# ft600hx4k.net
KiCad netlist of a schematic drawn in Altium Designer
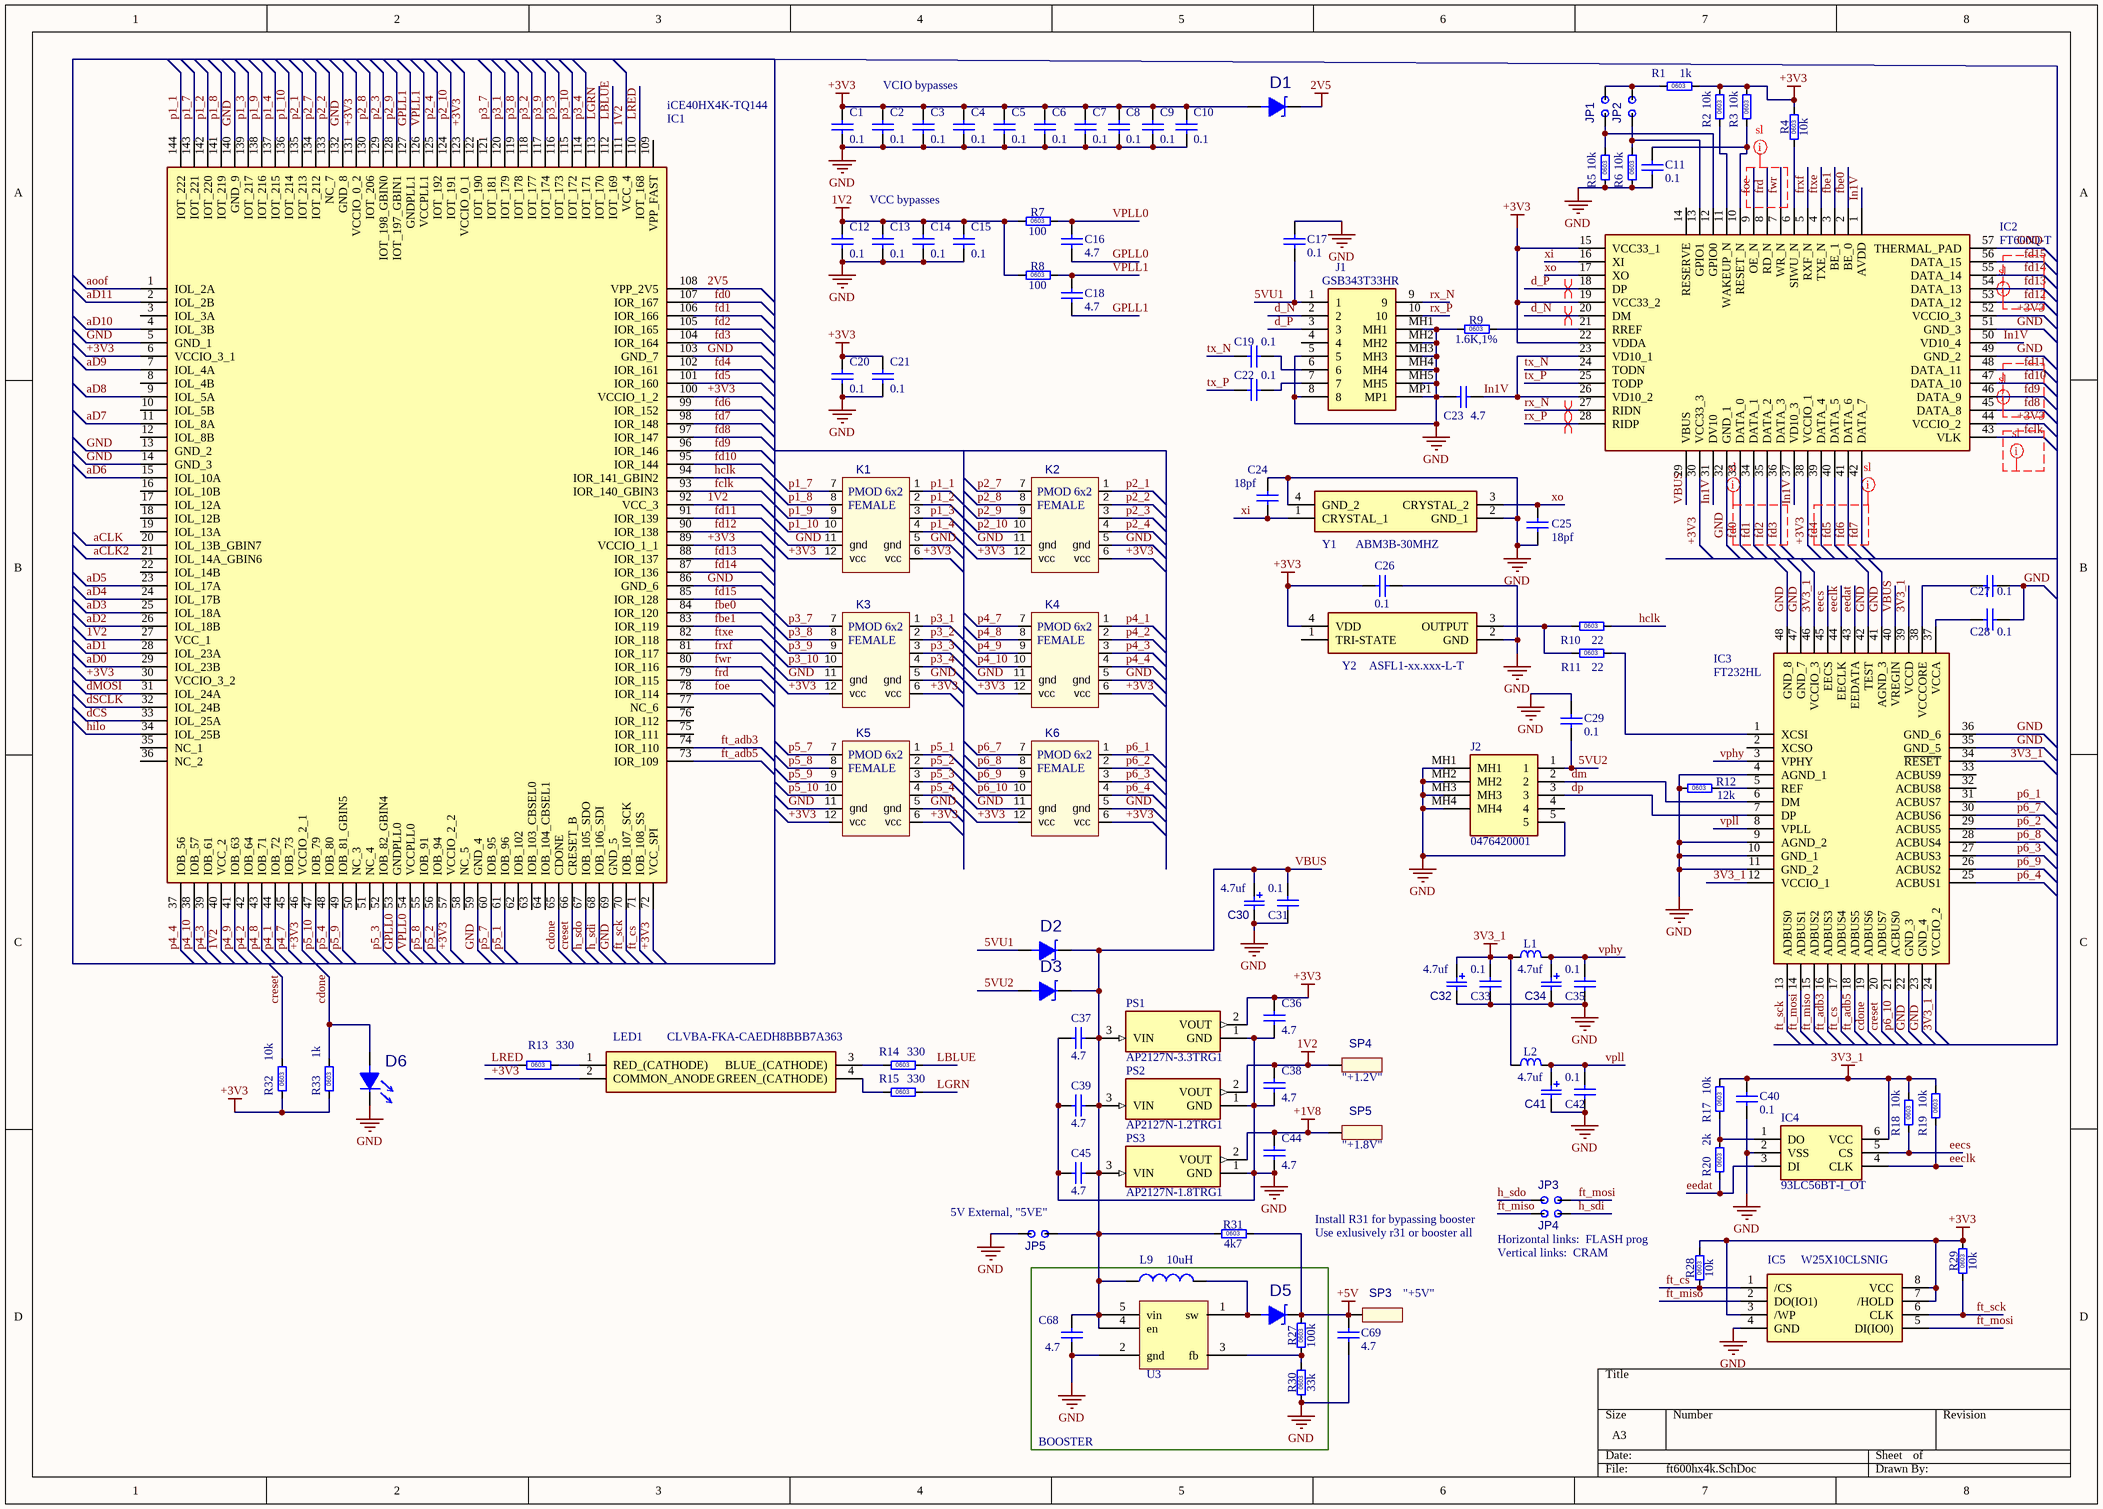
[diagram p0: ft600hx4k.SchDoc]

(export (version "E")
  (design (tool "Eeschema 10.0.6"))
  (components
    (comp (ref "C1")
      (value "0.1")
      (footprint "SM0603 _3D_cap")
      (description "Capacitor  0603 inch")
      (fields (field (name "Comment") "cap0603") (field (name "PUBLISHER") "Altium Limited"))
      (libsource (lib "alt2017") (part "cap0603"))
    )
    (comp (ref "C2")
      (value "0.1")
      (footprint "SM0603 _3D_cap")
      (description "Capacitor  0603 inch")
      (fields (field (name "Comment") "cap0603") (field (name "PUBLISHER") "Altium Limited"))
      (libsource (lib "alt2017") (part "cap0603"))
    )
    (comp (ref "C3")
      (value "0.1")
      (footprint "SM0603 _3D_cap")
      (description "Capacitor  0603 inch")
      (fields (field (name "Comment") "cap0603") (field (name "PUBLISHER") "Altium Limited"))
      (libsource (lib "alt2017") (part "cap0603"))
    )
    (comp (ref "C4")
      (value "0.1")
      (footprint "SM0603 _3D_cap")
      (description "Capacitor  0603 inch")
      (fields (field (name "Comment") "cap0603") (field (name "PUBLISHER") "Altium Limited"))
      (libsource (lib "alt2017") (part "cap0603"))
    )
    (comp (ref "C5")
      (value "0.1")
      (footprint "SM0603 _3D_cap")
      (description "Capacitor  0603 inch")
      (fields (field (name "Comment") "cap0603") (field (name "PUBLISHER") "Altium Limited"))
      (libsource (lib "alt2017") (part "cap0603"))
    )
    (comp (ref "C6")
      (value "0.1")
      (footprint "SM0603 _3D_cap")
      (description "Capacitor  0603 inch")
      (fields (field (name "Comment") "cap0603") (field (name "PUBLISHER") "Altium Limited"))
      (libsource (lib "alt2017") (part "cap0603"))
    )
    (comp (ref "C7")
      (value "0.1")
      (footprint "SM0603 _3D_cap")
      (description "Capacitor  0603 inch")
      (fields (field (name "Comment") "cap0603") (field (name "PUBLISHER") "Altium Limited"))
      (libsource (lib "alt2017") (part "cap0603"))
    )
    (comp (ref "C8")
      (value "0.1")
      (footprint "SM0603 _3D_cap")
      (description "Capacitor  0603 inch")
      (fields (field (name "Comment") "cap0603") (field (name "PUBLISHER") "Altium Limited"))
      (libsource (lib "alt2017") (part "cap0603"))
    )
    (comp (ref "C9")
      (value "0.1")
      (footprint "SM0603 _3D_cap")
      (description "Capacitor  0603 inch")
      (fields (field (name "Comment") "cap0603") (field (name "PUBLISHER") "Altium Limited"))
      (libsource (lib "alt2017") (part "cap0603"))
    )
    (comp (ref "C10")
      (value "0.1")
      (footprint "SM0603 _3D_cap")
      (description "Capacitor  0603 inch")
      (fields (field (name "Comment") "cap0603") (field (name "PUBLISHER") "Altium Limited"))
      (libsource (lib "alt2017") (part "cap0603"))
    )
    (comp (ref "C11")
      (value "0.1")
      (footprint "SM0603 _3D_cap")
      (description "Capacitor  0603 inch")
      (fields (field (name "Comment") "cap0603") (field (name "PUBLISHER") "Altium Limited"))
      (libsource (lib "alt2017") (part "cap0603"))
    )
    (comp (ref "C12")
      (value "0.1")
      (footprint "SM0603 _3D_cap")
      (description "Capacitor  0603 inch")
      (fields (field (name "Comment") "cap0603") (field (name "PUBLISHER") "Altium Limited"))
      (libsource (lib "alt2017") (part "cap0603"))
    )
    (comp (ref "C13")
      (value "0.1")
      (footprint "SM0603 _3D_cap")
      (description "Capacitor  0603 inch")
      (fields (field (name "Comment") "cap0603") (field (name "PUBLISHER") "Altium Limited"))
      (libsource (lib "alt2017") (part "cap0603"))
    )
    (comp (ref "C14")
      (value "0.1")
      (footprint "SM0603 _3D_cap")
      (description "Capacitor  0603 inch")
      (fields (field (name "Comment") "cap0603") (field (name "PUBLISHER") "Altium Limited"))
      (libsource (lib "alt2017") (part "cap0603"))
    )
    (comp (ref "C15")
      (value "0.1")
      (footprint "SM0603 _3D_cap")
      (description "Capacitor  0603 inch")
      (fields (field (name "Comment") "cap0603") (field (name "PUBLISHER") "Altium Limited"))
      (libsource (lib "alt2017") (part "cap0603"))
    )
    (comp (ref "C16")
      (value "4.7")
      (footprint "SM0603 _3D_cap")
      (description "Capacitor  0603 inch")
      (fields (field (name "Comment") "cap0603") (field (name "PUBLISHER") "Altium Limited"))
      (libsource (lib "alt2017") (part "cap0603"))
    )
    (comp (ref "C17")
      (value "0.1")
      (footprint "SM0603 _3D_cap")
      (description "Capacitor  0603 inch")
      (fields (field (name "Comment") "cap0603") (field (name "PUBLISHER") "Altium Limited"))
      (libsource (lib "alt2017") (part "cap0603"))
    )
    (comp (ref "C18")
      (value "4.7")
      (footprint "SM0603 _3D_cap")
      (description "Capacitor  0603 inch")
      (fields (field (name "Comment") "cap0603") (field (name "PUBLISHER") "Altium Limited"))
      (libsource (lib "alt2017") (part "cap0603"))
    )
    (comp (ref "C19")
      (value "0.1")
      (footprint "SM0603 _3D_cap")
      (description "Capacitor  0603 inch")
      (fields (field (name "Comment") "cap0603") (field (name "PUBLISHER") "Altium Limited"))
      (libsource (lib "alt2017") (part "cap0603"))
    )
    (comp (ref "C20")
      (value "0.1")
      (footprint "SM0603 _3D_cap")
      (description "Capacitor  0603 inch")
      (fields (field (name "Comment") "cap0603") (field (name "PUBLISHER") "Altium Limited"))
      (libsource (lib "alt2017") (part "cap0603"))
    )
    (comp (ref "C21")
      (value "0.1")
      (footprint "SM0603 _3D_cap")
      (description "Capacitor  0603 inch")
      (fields (field (name "Comment") "cap0603") (field (name "PUBLISHER") "Altium Limited"))
      (libsource (lib "alt2017") (part "cap0603"))
    )
    (comp (ref "C22")
      (value "0.1")
      (footprint "SM0603 _3D_cap")
      (description "Capacitor  0603 inch")
      (fields (field (name "Comment") "cap0603") (field (name "PUBLISHER") "Altium Limited"))
      (libsource (lib "alt2017") (part "cap0603"))
    )
    (comp (ref "C23")
      (value "4.7")
      (footprint "SM0603 _3D_cap")
      (description "Capacitor  0603 inch")
      (fields (field (name "Comment") "cap0603") (field (name "PUBLISHER") "Altium Limited"))
      (libsource (lib "alt2017") (part "cap0603"))
    )
    (comp (ref "C24")
      (value "18pf")
      (footprint "SM0603 _3D_cap")
      (description "Capacitor  0603 inch")
      (fields (field (name "Comment") "cap0603") (field (name "PUBLISHER") "Altium Limited"))
      (libsource (lib "alt2017") (part "cap0603"))
    )
    (comp (ref "C25")
      (value "18pf")
      (footprint "SM0603 _3D_cap")
      (description "Capacitor  0603 inch")
      (fields (field (name "Comment") "cap0603") (field (name "PUBLISHER") "Altium Limited"))
      (libsource (lib "alt2017") (part "cap0603"))
    )
    (comp (ref "C26")
      (value "0.1")
      (footprint "SM0603 _3D_cap")
      (description "Capacitor  0603 inch")
      (fields (field (name "Comment") "cap0603") (field (name "PUBLISHER") "Altium Limited"))
      (libsource (lib "alt2017") (part "cap0603"))
    )
    (comp (ref "C27")
      (value "0.1")
      (footprint "SM0603 _3D_cap")
      (description "Capacitor  0603 inch")
      (fields (field (name "Comment") "cap0603") (field (name "PUBLISHER") "Altium Limited"))
      (libsource (lib "alt2017") (part "cap0603"))
    )
    (comp (ref "C28")
      (value "0.1")
      (footprint "SM0603 _3D_cap")
      (description "Capacitor  0603 inch")
      (fields (field (name "Comment") "cap0603") (field (name "PUBLISHER") "Altium Limited"))
      (libsource (lib "alt2017") (part "cap0603"))
    )
    (comp (ref "C29")
      (value "0.1")
      (footprint "SM0603 _3D_cap")
      (description "Capacitor  0603 inch")
      (fields (field (name "Comment") "cap0603") (field (name "PUBLISHER") "Altium Limited"))
      (libsource (lib "alt2017") (part "cap0603"))
    )
    (comp (ref "C30")
      (value "CAP_POL_SMA")
      (footprint "CAP_POL_SMA (3216)")
      (description "CAP_POL_SMA(3216)")
      (fields (field (name "ALTIUM_UNNAMED_1") "4.7uf"))
      (libsource (lib "alt2017") (part "CAP_POL_SMA"))
    )
    (comp (ref "C31")
      (value "0.1")
      (footprint "SM0603 _3D_cap")
      (description "Capacitor  0603 inch")
      (fields (field (name "Comment") "cap0603") (field (name "PUBLISHER") "Altium Limited"))
      (libsource (lib "alt2017") (part "cap0603"))
    )
    (comp (ref "C32")
      (value "CAP_POL_SMA")
      (footprint "CAP_POL_SMA (3216)")
      (description "CAP_POL_SMA(3216)")
      (fields (field (name "ALTIUM_UNNAMED_1") "4.7uf"))
      (libsource (lib "alt2017") (part "CAP_POL_SMA"))
    )
    (comp (ref "C33")
      (value "0.1")
      (footprint "SM0603 _3D_cap")
      (description "Capacitor  0603 inch")
      (fields (field (name "Comment") "cap0603") (field (name "PUBLISHER") "Altium Limited"))
      (libsource (lib "alt2017") (part "cap0603"))
    )
    (comp (ref "C34")
      (value "CAP_POL_SMA")
      (footprint "CAP_POL_SMA (3216)")
      (description "CAP_POL_SMA(3216)")
      (fields (field (name "ALTIUM_UNNAMED_1") "4.7uf"))
      (libsource (lib "alt2017") (part "CAP_POL_SMA"))
    )
    (comp (ref "C35")
      (value "0.1")
      (footprint "SM0603 _3D_cap")
      (description "Capacitor  0603 inch")
      (fields (field (name "Comment") "cap0603") (field (name "PUBLISHER") "Altium Limited"))
      (libsource (lib "alt2017") (part "cap0603"))
    )
    (comp (ref "C36")
      (value "4.7")
      (footprint "SM0603 _3D_cap")
      (description "Capacitor  0603 inch")
      (fields (field (name "Comment") "cap0603") (field (name "PUBLISHER") "Altium Limited"))
      (libsource (lib "alt2017") (part "cap0603"))
    )
    (comp (ref "C37")
      (value "4.7")
      (footprint "SM0603 _3D_cap")
      (description "Capacitor  0603 inch")
      (fields (field (name "Comment") "cap0603") (field (name "PUBLISHER") "Altium Limited"))
      (libsource (lib "alt2017") (part "cap0603"))
    )
    (comp (ref "C38")
      (value "4.7")
      (footprint "SM0603 _3D_cap")
      (description "Capacitor  0603 inch")
      (fields (field (name "Comment") "cap0603") (field (name "PUBLISHER") "Altium Limited"))
      (libsource (lib "alt2017") (part "cap0603"))
    )
    (comp (ref "C39")
      (value "4.7")
      (footprint "SM0603 _3D_cap")
      (description "Capacitor  0603 inch")
      (fields (field (name "Comment") "cap0603") (field (name "PUBLISHER") "Altium Limited"))
      (libsource (lib "alt2017") (part "cap0603"))
    )
    (comp (ref "C40")
      (value "0.1")
      (footprint "SM0603 _3D_cap")
      (description "Capacitor  0603 inch")
      (fields (field (name "Comment") "cap0603") (field (name "PUBLISHER") "Altium Limited"))
      (libsource (lib "alt2017") (part "cap0603"))
    )
    (comp (ref "C41")
      (value "CAP_POL_SMA")
      (footprint "CAP_POL_SMA (3216)")
      (description "CAP_POL_SMA(3216)")
      (fields (field (name "ALTIUM_UNNAMED_1") "4.7uf"))
      (libsource (lib "alt2017") (part "CAP_POL_SMA"))
    )
    (comp (ref "C42")
      (value "0.1")
      (footprint "SM0603 _3D_cap")
      (description "Capacitor  0603 inch")
      (fields (field (name "Comment") "cap0603") (field (name "PUBLISHER") "Altium Limited"))
      (libsource (lib "alt2017") (part "cap0603"))
    )
    (comp (ref "C44")
      (value "4.7")
      (footprint "SM0603 _3D_cap")
      (description "Capacitor  0603 inch")
      (fields (field (name "Comment") "cap0603") (field (name "PUBLISHER") "Altium Limited"))
      (libsource (lib "alt2017") (part "cap0603"))
    )
    (comp (ref "C45")
      (value "4.7")
      (footprint "SM0603 _3D_cap")
      (description "Capacitor  0603 inch")
      (fields (field (name "Comment") "cap0603") (field (name "PUBLISHER") "Altium Limited"))
      (libsource (lib "alt2017") (part "cap0603"))
    )
    (comp (ref "C68")
      (value "4.7")
      (footprint "SM0603 _3D_cap")
      (description "Capacitor  0603 inch")
      (fields (field (name "Comment") "cap0603") (field (name "PUBLISHER") "Altium Limited"))
      (libsource (lib "alt2017") (part "cap0603"))
    )
    (comp (ref "C69")
      (value "4.7")
      (footprint "SM0603 _3D_cap")
      (description "Capacitor  0603 inch")
      (fields (field (name "Comment") "cap0603") (field (name "PUBLISHER") "Altium Limited"))
      (libsource (lib "alt2017") (part "cap0603"))
    )
    (comp (ref "D1")
      (value "DiodeShottky_SOD323")
      (footprint "SOD323")
      (description "SOD323")
      (libsource (lib "alt2017") (part "DiodeShottky_SOD323"))
    )
    (comp (ref "D2")
      (value "DiodeShottky_SOD323")
      (footprint "SOD323")
      (description "SOD323")
      (libsource (lib "alt2017") (part "DiodeShottky_SOD323"))
    )
    (comp (ref "D3")
      (value "DiodeShottky_SOD323")
      (footprint "SOD323")
      (description "SOD323")
      (libsource (lib "alt2017") (part "DiodeShottky_SOD323"))
    )
    (comp (ref "D5")
      (value "DiodeShottky_SOD323")
      (footprint "SOD323")
      (description "SOD323")
      (libsource (lib "alt2017") (part "DiodeShottky_SOD323"))
    )
    (comp (ref "D6")
      (value "LIGHT_SM0805")
      (footprint "SM0805_diode")
      (libsource (lib "alt2017") (part "LIGHT_SM0805"))
    )
    (comp (ref "IC1")
      (value "iCE40HX4K-TQ144")
      (footprint "SamacSys:QFP50P2200X2200X160-144N")
      (description "Integrated Circuit")
      (fields
        (field (name "MOUSER PART NUMBER") "842-ICE40HX4K-TQ144")
        (field (name "ARROW PART NUMBER") "ICE40HX4K-TQ144")
      )
      (libsource (lib "*") (part "iCE40HX4K-TQ144"))
    )
    (comp (ref "IC2")
      (value "FT600Q-T")
      (footprint "SamacSys:QFN40P700X700X90-57N-D")
      (description "Integrated Circuit")
      (fields (field (name "MOUSER PART NUMBER") "895-FT600Q-T"))
      (libsource (lib "SamacSys") (part "FT600Q-T"))
    )
    (comp (ref "IC3")
      (value "FT232HL")
      (footprint "SamacSys:QFP50P900X900X160-48N")
      (description "Integrated Circuit")
      (fields
        (field (name "MANUFACTURER_PART_NUMBER") "FT232HL-REEL")
        (field (name "MOUSER PART NUMBER") "895-FT232HL-REEL")
      )
      (libsource (lib "*") (part "FT232HL-REEL"))
    )
    (comp (ref "IC4")
      (value "93LC56BT-I_OT")
      (footprint "SamacSys:SOT95P270X145-6N")
      (description "Integrated Circuit")
      (fields
        (field (name "MANUFACTURER_PART_NUMBER") "93LC56BT-I/OT")
        (field (name "MOUSER PART NUMBER") "579-93LC56BT-I/OT")
      )
      (libsource (lib "*") (part "93LC56BT-I_OT"))
    )
    (comp (ref "IC5")
      (value "W25X10CLSNIG")
      (footprint "SamacSys:SOIC127P600X175-8N")
      (description "Integrated Circuit")
      (fields (field (name "MOUSER PART NUMBER") "454-W25X10CLSNIG"))
      (libsource (lib "*") (part "W25X10CLSNIG"))
    )
    (comp (ref "J1")
      (value "GSB343T33HR")
      (footprint "SamacSys:GSB343T33HR")
      (description "Connector")
      (fields (field (name "MOUSER PART NUMBER") "523-GSB343T33HR"))
      (libsource (lib "*") (part "GSB343T33HR"))
    )
    (comp (ref "J2")
      (value "0476420001")
      (footprint "SamacSys:0476420001")
      (description "Connector")
      (libsource (lib "*") (part "0476420001"))
    )
    (comp (ref "JP1") (value "JUMPER2") (footprint "JUMPER2") (libsource (lib "alt2017") (part "JUMPER2")))
    (comp (ref "JP2") (value "JUMPER2") (footprint "JUMPER2") (libsource (lib "alt2017") (part "JUMPER2")))
    (comp (ref "JP3") (value "JUMPER2") (footprint "JUMPER2") (libsource (lib "alt2017") (part "JUMPER2")))
    (comp (ref "JP4") (value "JUMPER2") (footprint "JUMPER2") (libsource (lib "alt2017") (part "JUMPER2")))
    (comp (ref "JP5") (value "JUMPER2") (footprint "JUMPER2") (libsource (lib "alt2017") (part "JUMPER2")))
    (comp (ref "K1")
      (value "PMOD_6x2_ra_female")
      (footprint "PMOD_6x2_RA_FEMALE")
      (description "PMOD_6x2_right_angle")
      (libsource (lib "alt_vovan") (part "PMOD_6x2_ra_female"))
    )
    (comp (ref "K2")
      (value "PMOD_6x2_ra_female")
      (footprint "PMOD_6x2_RA_FEMALE")
      (description "PMOD_6x2_right_angle")
      (libsource (lib "alt_vovan") (part "PMOD_6x2_ra_female"))
    )
    (comp (ref "K3")
      (value "PMOD_6x2_ra_female")
      (footprint "PMOD_6x2_RA_FEMALE")
      (description "PMOD_6x2_right_angle")
      (libsource (lib "alt_vovan") (part "PMOD_6x2_ra_female"))
    )
    (comp (ref "K4")
      (value "PMOD_6x2_ra_female")
      (footprint "PMOD_6x2_RA_FEMALE")
      (description "PMOD_6x2_right_angle")
      (libsource (lib "alt_vovan") (part "PMOD_6x2_ra_female"))
    )
    (comp (ref "K5")
      (value "PMOD_6x2_ra_female")
      (footprint "PMOD_6x2_RA_FEMALE")
      (description "PMOD_6x2_right_angle")
      (libsource (lib "alt_vovan") (part "PMOD_6x2_ra_female"))
    )
    (comp (ref "K6")
      (value "PMOD_6x2_ra_female")
      (footprint "PMOD_6x2_RA_FEMALE")
      (description "PMOD_6x2_right_angle")
      (libsource (lib "alt_vovan") (part "PMOD_6x2_ra_female"))
    )
    (comp (ref "L1")
      (value "75R@100MHz")
      (footprint "SM0603_3D_res")
      (description "chip inductance 0603")
      (fields
        (field (name "PART NUMBER") "IND0805_MURATA_BLM21BB750SN1D")
        (field (name "POWER") "700mA")
        (field (name "AUTHOR") "S. Jafar")
      )
      (libsource (lib "alt_vovan") (part "chip inductance 0603"))
    )
    (comp (ref "L2")
      (value "75R@100MHz")
      (footprint "SM0603_3D_res")
      (description "chip inductance 0603")
      (fields
        (field (name "PART NUMBER") "IND0805_MURATA_BLM21BB750SN1D")
        (field (name "POWER") "700mA")
        (field (name "AUTHOR") "S. Jafar")
      )
      (libsource (lib "alt_vovan") (part "chip inductance 0603"))
    )
    (comp (ref "L9")
      (value "inductance SMT 3.2x4.5 mm")
      (footprint "inductor_LQH43PN")
      (fields (field (name "ALTIUM_UNNAMED_1") "10uH"))
      (libsource (lib "alt2017") (part "inductor_LQH43PN"))
    )
    (comp (ref "LED1")
      (value "CLVBA-FKA-CAEDH8BBB7A363")
      (footprint "SamacSys:CLVBAFKACAEDH8BBB7A363")
      (description "LED")
      (fields (field (name "MOUSER PART NUMBER") "941-VBAFKACAEDH8B7A3"))
      (libsource (lib "*") (part "CLVBA-FKA-CAEDH8BBB7A363"))
    )
    (comp (ref "PS1")
      (value "AP2127N-3.3TRG1")
      (footprint "SamacSys:SOT89P240X110-3N")
      (description "Power Supply")
      (fields (field (name "MOUSER PART NUMBER") "621-AP2127N-3.3TRG1"))
      (libsource (lib "*") (part "AP2127N-3.3TRG1"))
    )
    (comp (ref "PS2")
      (value "AP2127N-1.2TRG1")
      (footprint "SamacSys:SOT89P240X110-3N")
      (description "Power Supply")
      (fields
        (field (name "MANUFACTURER_PART_NUMBER") "AP2127N-3.3TRG1")
        (field (name "MOUSER PART NUMBER") "621-AP2127N-3.3TRG1")
      )
      (libsource (lib "*") (part "AP2127N-3.3TRG1"))
    )
    (comp (ref "PS3")
      (value "AP2127N-1.8TRG1")
      (footprint "SamacSys:SOT89P240X110-3N")
      (description "Power Supply")
      (fields
        (field (name "MANUFACTURER_PART_NUMBER") "AP2127N-3.3TRG1")
        (field (name "MOUSER PART NUMBER") "621-AP2127N-3.3TRG1")
      )
      (libsource (lib "*") (part "AP2127N-3.3TRG1"))
    )
    (comp (ref "R1")
      (value "1k")
      (footprint "SM0603_3D_res")
      (description "Res_0603_EU")
      (fields
        (field (name "PART NUMBER") "R1206_4K7_1%_0.25W_100PPM")
        (field (name "POWER") "0.25W")
        (field (name "AUTHOR") "CERN DEM JLC")
      )
      (libsource (lib "alt_vovan") (part "Res_0603_EU"))
    )
    (comp (ref "R2")
      (value "10k")
      (footprint "SM0603_3D_res")
      (description "Res_0603_EU")
      (fields
        (field (name "PART NUMBER") "R1206_4K7_1%_0.25W_100PPM")
        (field (name "POWER") "0.25W")
        (field (name "AUTHOR") "CERN DEM JLC")
      )
      (libsource (lib "alt_vovan") (part "Res_0603_EU"))
    )
    (comp (ref "R3")
      (value "10k")
      (footprint "SM0603_3D_res")
      (description "Res_0603_EU")
      (fields
        (field (name "PART NUMBER") "R1206_4K7_1%_0.25W_100PPM")
        (field (name "POWER") "0.25W")
        (field (name "AUTHOR") "CERN DEM JLC")
      )
      (libsource (lib "alt_vovan") (part "Res_0603_EU"))
    )
    (comp (ref "R4")
      (value "10k")
      (footprint "SM0603_3D_res")
      (description "Res_0603_EU")
      (fields
        (field (name "PART NUMBER") "R1206_4K7_1%_0.25W_100PPM")
        (field (name "POWER") "0.25W")
        (field (name "AUTHOR") "CERN DEM JLC")
      )
      (libsource (lib "alt_vovan") (part "Res_0603_EU"))
    )
    (comp (ref "R5")
      (value "10k")
      (footprint "SM0603_3D_res")
      (description "Res_0603_EU")
      (fields
        (field (name "PART NUMBER") "R1206_4K7_1%_0.25W_100PPM")
        (field (name "POWER") "0.25W")
        (field (name "AUTHOR") "CERN DEM JLC")
      )
      (libsource (lib "alt_vovan") (part "Res_0603_EU"))
    )
    (comp (ref "R6")
      (value "10k")
      (footprint "SM0603_3D_res")
      (description "Res_0603_EU")
      (fields
        (field (name "PART NUMBER") "R1206_4K7_1%_0.25W_100PPM")
        (field (name "POWER") "0.25W")
        (field (name "AUTHOR") "CERN DEM JLC")
      )
      (libsource (lib "alt_vovan") (part "Res_0603_EU"))
    )
    (comp (ref "R7")
      (value "100")
      (footprint "SM0603_3D_res")
      (description "Res_0603_EU")
      (fields
        (field (name "PART NUMBER") "R1206_4K7_1%_0.25W_100PPM")
        (field (name "POWER") "0.25W")
        (field (name "AUTHOR") "CERN DEM JLC")
      )
      (libsource (lib "alt_vovan") (part "Res_0603_EU"))
    )
    (comp (ref "R8")
      (value "100")
      (footprint "SM0603_3D_res")
      (description "Res_0603_EU")
      (fields
        (field (name "PART NUMBER") "R1206_4K7_1%_0.25W_100PPM")
        (field (name "POWER") "0.25W")
        (field (name "AUTHOR") "CERN DEM JLC")
      )
      (libsource (lib "alt_vovan") (part "Res_0603_EU"))
    )
    (comp (ref "R9")
      (value "1.6K,1%")
      (footprint "SM0603_3D_res")
      (description "Res_0603_EU")
      (fields
        (field (name "PART NUMBER") "R1206_4K7_1%_0.25W_100PPM")
        (field (name "POWER") "0.25W")
        (field (name "AUTHOR") "CERN DEM JLC")
      )
      (libsource (lib "alt_vovan") (part "Res_0603_EU"))
    )
    (comp (ref "R10")
      (value "22")
      (footprint "SM0603_3D_res")
      (description "Res_0603_EU")
      (fields
        (field (name "PART NUMBER") "R1206_4K7_1%_0.25W_100PPM")
        (field (name "POWER") "0.25W")
        (field (name "AUTHOR") "CERN DEM JLC")
      )
      (libsource (lib "alt_vovan") (part "Res_0603_EU"))
    )
    (comp (ref "R11")
      (value "22")
      (footprint "SM0603_3D_res")
      (description "Res_0603_EU")
      (fields
        (field (name "PART NUMBER") "R1206_4K7_1%_0.25W_100PPM")
        (field (name "POWER") "0.25W")
        (field (name "AUTHOR") "CERN DEM JLC")
      )
      (libsource (lib "alt_vovan") (part "Res_0603_EU"))
    )
    (comp (ref "R12")
      (value "12k")
      (footprint "SM0603_3D_res")
      (description "Res_0603_EU")
      (fields
        (field (name "PART NUMBER") "R1206_4K7_1%_0.25W_100PPM")
        (field (name "POWER") "0.25W")
        (field (name "AUTHOR") "CERN DEM JLC")
      )
      (libsource (lib "alt_vovan") (part "Res_0603_EU"))
    )
    (comp (ref "R13")
      (value "330")
      (footprint "SM0603_3D_res")
      (description "Res_0603_EU")
      (fields
        (field (name "PART NUMBER") "R1206_4K7_1%_0.25W_100PPM")
        (field (name "POWER") "0.25W")
        (field (name "AUTHOR") "CERN DEM JLC")
      )
      (libsource (lib "alt_vovan") (part "Res_0603_EU"))
    )
    (comp (ref "R14")
      (value "330")
      (footprint "SM0603_3D_res")
      (description "Res_0603_EU")
      (fields
        (field (name "PART NUMBER") "R1206_4K7_1%_0.25W_100PPM")
        (field (name "POWER") "0.25W")
        (field (name "AUTHOR") "CERN DEM JLC")
      )
      (libsource (lib "alt_vovan") (part "Res_0603_EU"))
    )
    (comp (ref "R15")
      (value "330")
      (footprint "SM0603_3D_res")
      (description "Res_0603_EU")
      (fields
        (field (name "PART NUMBER") "R1206_4K7_1%_0.25W_100PPM")
        (field (name "POWER") "0.25W")
        (field (name "AUTHOR") "CERN DEM JLC")
      )
      (libsource (lib "alt_vovan") (part "Res_0603_EU"))
    )
    (comp (ref "R17")
      (value "10k")
      (footprint "SM0603_3D_res")
      (description "Res_0603_EU")
      (fields
        (field (name "PART NUMBER") "R1206_4K7_1%_0.25W_100PPM")
        (field (name "POWER") "0.25W")
        (field (name "AUTHOR") "CERN DEM JLC")
      )
      (libsource (lib "alt_vovan") (part "Res_0603_EU"))
    )
    (comp (ref "R18")
      (value "10k")
      (footprint "SM0603_3D_res")
      (description "Res_0603_EU")
      (fields
        (field (name "PART NUMBER") "R1206_4K7_1%_0.25W_100PPM")
        (field (name "POWER") "0.25W")
        (field (name "AUTHOR") "CERN DEM JLC")
      )
      (libsource (lib "alt_vovan") (part "Res_0603_EU"))
    )
    (comp (ref "R19")
      (value "10k")
      (footprint "SM0603_3D_res")
      (description "Res_0603_EU")
      (fields
        (field (name "PART NUMBER") "R1206_4K7_1%_0.25W_100PPM")
        (field (name "POWER") "0.25W")
        (field (name "AUTHOR") "CERN DEM JLC")
      )
      (libsource (lib "alt_vovan") (part "Res_0603_EU"))
    )
    (comp (ref "R20")
      (value "2k")
      (footprint "SM0603_3D_res")
      (description "Res_0603_EU")
      (fields
        (field (name "PART NUMBER") "R1206_4K7_1%_0.25W_100PPM")
        (field (name "POWER") "0.25W")
        (field (name "AUTHOR") "CERN DEM JLC")
      )
      (libsource (lib "alt_vovan") (part "Res_0603_EU"))
    )
    (comp (ref "R27")
      (value "100k")
      (footprint "SM0603_3D_res")
      (description "Res_0603_EU")
      (fields
        (field (name "PART NUMBER") "R1206_4K7_1%_0.25W_100PPM")
        (field (name "POWER") "0.25W")
        (field (name "AUTHOR") "CERN DEM JLC")
      )
      (libsource (lib "alt_vovan") (part "Res_0603_EU"))
    )
    (comp (ref "R28")
      (value "10k")
      (footprint "SM0603_3D_res")
      (description "Res_0603_EU")
      (fields
        (field (name "PART NUMBER") "R1206_4K7_1%_0.25W_100PPM")
        (field (name "POWER") "0.25W")
        (field (name "AUTHOR") "CERN DEM JLC")
      )
      (libsource (lib "alt_vovan") (part "Res_0603_EU"))
    )
    (comp (ref "R29")
      (value "10k")
      (footprint "SM0603_3D_res")
      (description "Res_0603_EU")
      (fields
        (field (name "PART NUMBER") "R1206_4K7_1%_0.25W_100PPM")
        (field (name "POWER") "0.25W")
        (field (name "AUTHOR") "CERN DEM JLC")
      )
      (libsource (lib "alt_vovan") (part "Res_0603_EU"))
    )
    (comp (ref "R30")
      (value "33k")
      (footprint "SM0603_3D_res")
      (description "Res_0603_EU")
      (fields
        (field (name "PART NUMBER") "R1206_4K7_1%_0.25W_100PPM")
        (field (name "POWER") "0.25W")
        (field (name "AUTHOR") "CERN DEM JLC")
      )
      (libsource (lib "alt_vovan") (part "Res_0603_EU"))
    )
    (comp (ref "R31")
      (value "4k7")
      (footprint "SM0603_3D_res")
      (description "Res_0603_EU")
      (fields
        (field (name "PART NUMBER") "R1206_4K7_1%_0.25W_100PPM")
        (field (name "POWER") "0.25W")
        (field (name "AUTHOR") "CERN DEM JLC")
      )
      (libsource (lib "alt_vovan") (part "Res_0603_EU"))
    )
    (comp (ref "R32")
      (value "10k")
      (footprint "SM0603_3D_res")
      (description "Res_0603_EU")
      (fields
        (field (name "PART NUMBER") "R1206_4K7_1%_0.25W_100PPM")
        (field (name "POWER") "0.25W")
        (field (name "AUTHOR") "CERN DEM JLC")
      )
      (libsource (lib "alt_vovan") (part "Res_0603_EU"))
    )
    (comp (ref "R33")
      (value "1k")
      (footprint "SM0603_3D_res")
      (description "Res_0603_EU")
      (fields
        (field (name "PART NUMBER") "R1206_4K7_1%_0.25W_100PPM")
        (field (name "POWER") "0.25W")
        (field (name "AUTHOR") "CERN DEM JLC")
      )
      (libsource (lib "alt_vovan") (part "Res_0603_EU"))
    )
    (comp (ref "SP3")
      (value "\"+5V\"")
      (footprint "SolderPad_D1mm _round")
      (description "for finger touch")
      (fields (field (name "Comment") "SolderPad D1mm_round"))
      (libsource (lib "alt2017") (part "SolderPad D1mm_round"))
    )
    (comp (ref "SP4")
      (value "\"+1.2V\"")
      (footprint "SolderPad_D1mm _round")
      (description "for finger touch")
      (fields (field (name "Comment") "SolderPad D1mm_round"))
      (libsource (lib "alt2017") (part "SolderPad D1mm_round"))
    )
    (comp (ref "SP5")
      (value "\"+1.8V\"")
      (footprint "SolderPad_D1mm _round")
      (description "for finger touch")
      (fields (field (name "Comment") "SolderPad D1mm_round"))
      (libsource (lib "alt2017") (part "SolderPad D1mm_round"))
    )
    (comp (ref "U3")
      (value "step up sot23-5")
      (footprint "SOT-23_5")
      (libsource (lib "alt2017") (part "TPS61040"))
    )
    (comp (ref "Y1")
      (value "ABM3B-30MHZ")
      (footprint "SamacSys:ABM3B")
      (description "Crystal or Oscillator")
      (fields
        (field (name "MANUFACTURER_PART_NUMBER") "ABM3B-11.0592MHZ-10-1-U-T")
        (field (name "MOUSER PART NUMBER") "815-ABM3B-11.0592-T")
      )
      (libsource (lib "*") (part "ABM3B-11.0592MHZ-10-1-U-T"))
    )
    (comp (ref "Y2")
      (value "ASFL1-xx.xxx-L-T")
      (footprint "SamacSys:ASFL125000MHZLT")
      (description "Crystal or Oscillator")
      (fields
        (field (name "MANUFACTURER_PART_NUMBER") "ASFL1-25.000MHZ-L-T")
        (field (name "MOUSER PART NUMBER") "815-ASFL1-25-L-T")
      )
      (libsource (lib "*") (part "ASFL1-25.000MHZ-L-T"))
    )
  )
  (nets
    (net (code "1") (name "+1V8") (class "Default")
      (node (ref "C44") (pin "1") (pinfunction "1_1") (pintype "passive"))
      (node (ref "PS3") (pin "2") (pinfunction "VOUT_2") (pintype "output"))
      (node (ref "SP5") (pin "1") (pinfunction "1_1") (pintype "passive"))
    )
    (net (code "2") (name "+3V3") (class "Default")
      (node (ref "C1") (pin "2") (pinfunction "2_2") (pintype "passive"))
      (node (ref "C10") (pin "2") (pinfunction "2_2") (pintype "passive"))
      (node (ref "C2") (pin "2") (pinfunction "2_2") (pintype "passive"))
      (node (ref "C20") (pin "2") (pinfunction "2_2") (pintype "passive"))
      (node (ref "C21") (pin "2") (pinfunction "2_2") (pintype "passive"))
      (node (ref "C26") (pin "1") (pinfunction "1_1") (pintype "passive"))
      (node (ref "C3") (pin "2") (pinfunction "2_2") (pintype "passive"))
      (node (ref "C36") (pin "1") (pinfunction "1_1") (pintype "passive"))
      (node (ref "C4") (pin "2") (pinfunction "2_2") (pintype "passive"))
      (node (ref "C5") (pin "2") (pinfunction "2_2") (pintype "passive"))
      (node (ref "C6") (pin "2") (pinfunction "2_2") (pintype "passive"))
      (node (ref "C7") (pin "2") (pinfunction "2_2") (pintype "passive"))
      (node (ref "C8") (pin "2") (pinfunction "2_2") (pintype "passive"))
      (node (ref "C9") (pin "2") (pinfunction "2_2") (pintype "passive"))
      (node (ref "D1") (pin "1") (pinfunction "a_1") (pintype "passive"))
      (node (ref "IC1") (pin "100") (pinfunction "VCCIO_1_2_100") (pintype "passive"))
      (node (ref "IC1") (pin "123") (pinfunction "VCCIO_0_1_123") (pintype "passive"))
      (node (ref "IC1") (pin "131") (pinfunction "VCCIO_0_2_131") (pintype "passive"))
      (node (ref "IC1") (pin "30") (pinfunction "VCCIO_3_2_30") (pintype "passive"))
      (node (ref "IC1") (pin "46") (pinfunction "VCCIO_2_1_46") (pintype "passive"))
      (node (ref "IC1") (pin "57") (pinfunction "VCCIO_2_2_57") (pintype "passive"))
      (node (ref "IC1") (pin "6") (pinfunction "VCCIO_3_1_6") (pintype "passive"))
      (node (ref "IC1") (pin "72") (pinfunction "VCC_SPI_72") (pintype "passive"))
      (node (ref "IC1") (pin "89") (pinfunction "VCCIO_1_1_89") (pintype "passive"))
      (node (ref "IC2") (pin "15") (pinfunction "VCC33_1_15") (pintype "passive"))
      (node (ref "IC2") (pin "19") (pinfunction "VCC33_2_19") (pintype "passive"))
      (node (ref "IC2") (pin "22") (pinfunction "VDDA_22") (pintype "passive"))
      (node (ref "IC2") (pin "30") (pinfunction "VCC33_3_30") (pintype "passive"))
      (node (ref "IC2") (pin "38") (pinfunction "VCCIO_1_38") (pintype "passive"))
      (node (ref "IC2") (pin "44") (pinfunction "VCCIO_2_44") (pintype "passive"))
      (node (ref "IC2") (pin "52") (pinfunction "VCCIO_3_52") (pintype "passive"))
      (node (ref "IC5") (pin "3") (pinfunction "/WP_3") (pintype "passive"))
      (node (ref "IC5") (pin "7") (pinfunction "/HOLD_7") (pintype "passive"))
      (node (ref "IC5") (pin "8") (pinfunction "VCC_8") (pintype "passive"))
      (node (ref "K1") (pin "12") (pinfunction "vcc_12") (pintype "passive"))
      (node (ref "K1") (pin "6") (pinfunction "vcc_6") (pintype "passive"))
      (node (ref "K2") (pin "12") (pinfunction "vcc_12") (pintype "passive"))
      (node (ref "K2") (pin "6") (pinfunction "vcc_6") (pintype "passive"))
      (node (ref "K3") (pin "12") (pinfunction "vcc_12") (pintype "passive"))
      (node (ref "K3") (pin "6") (pinfunction "vcc_6") (pintype "passive"))
      (node (ref "K4") (pin "12") (pinfunction "vcc_12") (pintype "passive"))
      (node (ref "K4") (pin "6") (pinfunction "vcc_6") (pintype "passive"))
      (node (ref "K5") (pin "12") (pinfunction "vcc_12") (pintype "passive"))
      (node (ref "K5") (pin "6") (pinfunction "vcc_6") (pintype "passive"))
      (node (ref "K6") (pin "12") (pinfunction "vcc_12") (pintype "passive"))
      (node (ref "K6") (pin "6") (pinfunction "vcc_6") (pintype "passive"))
      (node (ref "LED1") (pin "2") (pinfunction "COMMON_ANODE_2") (pintype "passive"))
      (node (ref "PS1") (pin "2") (pinfunction "VOUT_2") (pintype "output"))
      (node (ref "R1") (pin "2") (pinfunction "2_2") (pintype "passive"))
      (node (ref "R2") (pin "2") (pinfunction "2_2") (pintype "passive"))
      (node (ref "R28") (pin "2") (pinfunction "2_2") (pintype "passive"))
      (node (ref "R29") (pin "2") (pinfunction "2_2") (pintype "passive"))
      (node (ref "R3") (pin "2") (pinfunction "2_2") (pintype "passive"))
      (node (ref "R32") (pin "1") (pinfunction "1_1") (pintype "passive"))
      (node (ref "R33") (pin "1") (pinfunction "1_1") (pintype "passive"))
      (node (ref "R4") (pin "2") (pinfunction "2_2") (pintype "passive"))
      (node (ref "Y2") (pin "4") (pinfunction "VDD_4") (pintype "passive"))
    )
    (net (code "3") (name "+5V") (class "Default")
      (node (ref "C69") (pin "2") (pinfunction "2_2") (pintype "passive"))
      (node (ref "D5") (pin "2") (pinfunction "k_2") (pintype "passive"))
      (node (ref "R27") (pin "2") (pinfunction "2_2") (pintype "passive"))
      (node (ref "R31") (pin "2") (pinfunction "2_2") (pintype "passive"))
      (node (ref "SP3") (pin "1") (pinfunction "1_1") (pintype "passive"))
    )
    (net (code "4") (name "/5VU1") (class "Default")
      (node (ref "C17") (pin "2") (pinfunction "2_2") (pintype "passive"))
      (node (ref "D2") (pin "1") (pinfunction "a_1") (pintype "passive"))
      (node (ref "J1") (pin "1") (pinfunction "1_1") (pintype "passive"))
    )
    (net (code "5") (name "/5VU2") (class "Default")
      (node (ref "C29") (pin "2") (pinfunction "2_2") (pintype "passive"))
      (node (ref "D3") (pin "1") (pinfunction "a_1") (pintype "passive"))
      (node (ref "J2") (pin "1") (pinfunction "1_1") (pintype "passive"))
    )
    (net (code "6") (name "/GPLL0") (class "Default")
      (node (ref "C16") (pin "2") (pinfunction "2_2") (pintype "passive"))
      (node (ref "IC1") (pin "53") (pinfunction "GNDPLL0_53") (pintype "passive"))
    )
    (net (code "7") (name "/GPLL1") (class "Default")
      (node (ref "C18") (pin "2") (pinfunction "2_2") (pintype "passive"))
      (node (ref "IC1") (pin "127") (pinfunction "GNDPLL1_127") (pintype "passive"))
    )
    (net (code "8") (name "/In1V") (class "Default")
      (node (ref "C23") (pin "1") (pinfunction "1_1") (pintype "passive"))
      (node (ref "IC2") (pin "1") (pinfunction "AVDD_1") (pintype "passive"))
      (node (ref "IC2") (pin "23") (pinfunction "VD10_1_23") (pintype "passive"))
      (node (ref "IC2") (pin "26") (pinfunction "VD10_2_26") (pintype "passive"))
      (node (ref "IC2") (pin "31") (pinfunction "DV10_31") (pintype "passive"))
      (node (ref "IC2") (pin "37") (pinfunction "VD10_3_37") (pintype "passive"))
      (node (ref "IC2") (pin "50") (pinfunction "VD10_4_50") (pintype "passive"))
    )
    (net (code "9") (name "/LBLUE") (class "Default")
      (node (ref "IC1") (pin "112") (pinfunction "IOT_169_112") (pintype "passive"))
      (node (ref "R14") (pin "2") (pinfunction "2_2") (pintype "passive"))
    )
    (net (code "10") (name "/LGRN") (class "Default")
      (node (ref "IC1") (pin "113") (pinfunction "IOT_170_113") (pintype "passive"))
      (node (ref "R15") (pin "2") (pinfunction "2_2") (pintype "passive"))
    )
    (net (code "11") (name "/LRED") (class "Default")
      (node (ref "IC1") (pin "110") (pinfunction "IOT_168_110") (pintype "passive"))
      (node (ref "R13") (pin "1") (pinfunction "1_1") (pintype "passive"))
    )
    (net (code "12") (name "/VBUS") (class "Default")
      (node (ref "C30") (pin "1") (pinfunction "a_1") (pintype "passive"))
      (node (ref "C31") (pin "1") (pinfunction "1_1") (pintype "passive"))
      (node (ref "C37") (pin "1") (pinfunction "1_1") (pintype "passive"))
      (node (ref "C39") (pin "2") (pinfunction "2_2") (pintype "passive"))
      (node (ref "C45") (pin "2") (pinfunction "2_2") (pintype "passive"))
      (node (ref "C68") (pin "2") (pinfunction "2_2") (pintype "passive"))
      (node (ref "D2") (pin "2") (pinfunction "k_2") (pintype "passive"))
      (node (ref "D3") (pin "2") (pinfunction "k_2") (pintype "passive"))
      (node (ref "IC2") (pin "29") (pinfunction "VBUS_29") (pintype "passive"))
      (node (ref "IC3") (pin "40") (pinfunction "VREGIN_40") (pintype "passive"))
      (node (ref "JP5") (pin "1") (pinfunction "1_1") (pintype "passive"))
      (node (ref "L9") (pin "1") (pinfunction "1_1") (pintype "passive"))
      (node (ref "PS1") (pin "3") (pinfunction "VIN_3") (pintype "input"))
      (node (ref "PS2") (pin "3") (pinfunction "VIN_3") (pintype "input"))
      (node (ref "PS3") (pin "3") (pinfunction "VIN_3") (pintype "input"))
      (node (ref "R31") (pin "1") (pinfunction "1_1") (pintype "passive"))
      (node (ref "U3") (pin "4") (pinfunction "en_4") (pintype "passive"))
      (node (ref "U3") (pin "5") (pinfunction "vin_5") (pintype "passive"))
    )
    (net (code "13") (name "/VPLL0") (class "Default")
      (node (ref "C16") (pin "1") (pinfunction "1_1") (pintype "passive"))
      (node (ref "IC1") (pin "54") (pinfunction "VCCPLL0_54") (pintype "passive"))
      (node (ref "R7") (pin "2") (pinfunction "2_2") (pintype "passive"))
    )
    (net (code "14") (name "/VPLL1") (class "Default")
      (node (ref "C18") (pin "1") (pinfunction "1_1") (pintype "passive"))
      (node (ref "IC1") (pin "126") (pinfunction "VCCPLL1_126") (pintype "passive"))
      (node (ref "R8") (pin "2") (pinfunction "2_2") (pintype "passive"))
    )
    (net (code "15") (name "/aCLK") (class "Default")
      (node (ref "IC1") (pin "20") (pinfunction "IOL_13B_GBIN7_20") (pintype "passive"))
    )
    (net (code "16") (name "/aCLK2") (class "Default")
      (node (ref "IC1") (pin "21") (pinfunction "IOL_14A_GBIN6_21") (pintype "passive"))
    )
    (net (code "17") (name "/aD0") (class "Default")
      (node (ref "IC1") (pin "29") (pinfunction "IOL_23B_29") (pintype "passive"))
    )
    (net (code "18") (name "/aD1") (class "Default")
      (node (ref "IC1") (pin "28") (pinfunction "IOL_23A_28") (pintype "passive"))
    )
    (net (code "19") (name "/aD2") (class "Default")
      (node (ref "IC1") (pin "26") (pinfunction "IOL_18B_26") (pintype "passive"))
    )
    (net (code "20") (name "/aD3") (class "Default")
      (node (ref "IC1") (pin "25") (pinfunction "IOL_18A_25") (pintype "passive"))
    )
    (net (code "21") (name "/aD4") (class "Default")
      (node (ref "IC1") (pin "24") (pinfunction "IOL_17B_24") (pintype "passive"))
    )
    (net (code "22") (name "/aD5") (class "Default")
      (node (ref "IC1") (pin "23") (pinfunction "IOL_17A_23") (pintype "passive"))
    )
    (net (code "23") (name "/aD6") (class "Default")
      (node (ref "IC1") (pin "15") (pinfunction "IOL_10A_15") (pintype "passive"))
    )
    (net (code "24") (name "/aD7") (class "Default")
      (node (ref "IC1") (pin "11") (pinfunction "IOL_8A_11") (pintype "passive"))
    )
    (net (code "25") (name "/aD8") (class "Default")
      (node (ref "IC1") (pin "9") (pinfunction "IOL_5A_9") (pintype "passive"))
    )
    (net (code "26") (name "/aD9") (class "Default")
      (node (ref "IC1") (pin "7") (pinfunction "IOL_4A_7") (pintype "passive"))
    )
    (net (code "27") (name "/aD10") (class "Default")
      (node (ref "IC1") (pin "4") (pinfunction "IOL_3B_4") (pintype "passive"))
    )
    (net (code "28") (name "/aD11") (class "Default")
      (node (ref "IC1") (pin "2") (pinfunction "IOL_2B_2") (pintype "passive"))
    )
    (net (code "29") (name "/aoof") (class "Default")
      (node (ref "IC1") (pin "1") (pinfunction "IOL_2A_1") (pintype "passive"))
    )
    (net (code "30") (name "/cdone") (class "Default")
      (node (ref "D6") (pin "1") (pinfunction "a_1") (pintype "passive"))
      (node (ref "IC1") (pin "65") (pinfunction "CDONE_65") (pintype "passive"))
      (node (ref "IC3") (pin "19") (pinfunction "ADBUS6_19") (pintype "passive"))
      (node (ref "R33") (pin "2") (pinfunction "2_2") (pintype "passive"))
    )
    (net (code "31") (name "/creset") (class "Default")
      (node (ref "IC1") (pin "66") (pinfunction "CRESET_B_66") (pintype "passive"))
      (node (ref "IC3") (pin "20") (pinfunction "ADBUS7_20") (pintype "passive"))
      (node (ref "R32") (pin "2") (pinfunction "2_2") (pintype "passive"))
    )
    (net (code "32") (name "/dCS") (class "Default")
      (node (ref "IC1") (pin "33") (pinfunction "IOL_25A_33") (pintype "passive"))
    )
    (net (code "33") (name "/dMOSI") (class "Default")
      (node (ref "IC1") (pin "31") (pinfunction "IOL_24A_31") (pintype "passive"))
    )
    (net (code "34") (name "/dSCLK") (class "Default")
      (node (ref "IC1") (pin "32") (pinfunction "IOL_24B_32") (pintype "passive"))
    )
    (net (code "35") (name "/d_N") (class "Default")
      (node (ref "IC2") (pin "20") (pinfunction "DM_20") (pintype "passive"))
      (node (ref "J1") (pin "2") (pinfunction "2_2") (pintype "passive"))
    )
    (net (code "36") (name "/d_P") (class "Default")
      (node (ref "IC2") (pin "18") (pinfunction "DP_18") (pintype "passive"))
      (node (ref "J1") (pin "3") (pinfunction "3_3") (pintype "passive"))
    )
    (net (code "37") (name "/dm") (class "Default")
      (node (ref "IC3") (pin "6") (pinfunction "DM_6") (pintype "passive"))
      (node (ref "J2") (pin "2") (pinfunction "2_2") (pintype "passive"))
    )
    (net (code "38") (name "/dp") (class "Default")
      (node (ref "IC3") (pin "7") (pinfunction "DP_7") (pintype "passive"))
      (node (ref "J2") (pin "3") (pinfunction "3_3") (pintype "passive"))
    )
    (net (code "39") (name "/eeclk") (class "Default")
      (node (ref "IC3") (pin "44") (pinfunction "EECLK_44") (pintype "passive"))
      (node (ref "IC4") (pin "4") (pinfunction "CLK_4") (pintype "passive"))
      (node (ref "R19") (pin "1") (pinfunction "1_1") (pintype "passive"))
    )
    (net (code "40") (name "/eecs") (class "Default")
      (node (ref "IC3") (pin "45") (pinfunction "EECS_45") (pintype "passive"))
      (node (ref "IC4") (pin "5") (pinfunction "CS_5") (pintype "passive"))
      (node (ref "R18") (pin "1") (pinfunction "1_1") (pintype "passive"))
    )
    (net (code "41") (name "/eedat") (class "Default")
      (node (ref "IC3") (pin "43") (pinfunction "EEDATA_43") (pintype "passive"))
      (node (ref "IC4") (pin "3") (pinfunction "DI_3") (pintype "passive"))
      (node (ref "R20") (pin "1") (pinfunction "1_1") (pintype "passive"))
    )
    (net (code "42") (name "/fbe0") (class "Default")
      (node (ref "IC1") (pin "84") (pinfunction "IOR_120_84") (pintype "passive"))
      (node (ref "IC2") (pin "2") (pinfunction "BE_0_2") (pintype "passive"))
    )
    (net (code "43") (name "/fbe1") (class "Default")
      (node (ref "IC1") (pin "83") (pinfunction "IOR_119_83") (pintype "passive"))
      (node (ref "IC2") (pin "3") (pinfunction "BE_1_3") (pintype "passive"))
    )
    (net (code "44") (name "/fclk") (class "Default")
      (node (ref "IC1") (pin "93") (pinfunction "IOR_140_GBIN3_93") (pintype "passive"))
      (node (ref "IC2") (pin "43") (pinfunction "VLK_43") (pintype "passive"))
    )
    (net (code "45") (name "/fd0") (class "Default")
      (node (ref "IC1") (pin "107") (pinfunction "IOR_167_107") (pintype "passive"))
      (node (ref "IC2") (pin "33") (pinfunction "DATA_0_33") (pintype "passive"))
    )
    (net (code "46") (name "/fd1") (class "Default")
      (node (ref "IC1") (pin "106") (pinfunction "IOR_166_106") (pintype "passive"))
      (node (ref "IC2") (pin "34") (pinfunction "DATA_1_34") (pintype "passive"))
    )
    (net (code "47") (name "/fd2") (class "Default")
      (node (ref "IC1") (pin "105") (pinfunction "IOR_165_105") (pintype "passive"))
      (node (ref "IC2") (pin "35") (pinfunction "DATA_2_35") (pintype "passive"))
    )
    (net (code "48") (name "/fd3") (class "Default")
      (node (ref "IC1") (pin "104") (pinfunction "IOR_164_104") (pintype "passive"))
      (node (ref "IC2") (pin "36") (pinfunction "DATA_3_36") (pintype "passive"))
    )
    (net (code "49") (name "/fd4") (class "Default")
      (node (ref "IC1") (pin "102") (pinfunction "IOR_161_102") (pintype "passive"))
      (node (ref "IC2") (pin "39") (pinfunction "DATA_4_39") (pintype "passive"))
    )
    (net (code "50") (name "/fd5") (class "Default")
      (node (ref "IC1") (pin "101") (pinfunction "IOR_160_101") (pintype "passive"))
      (node (ref "IC2") (pin "40") (pinfunction "DATA_5_40") (pintype "passive"))
    )
    (net (code "51") (name "/fd6") (class "Default")
      (node (ref "IC1") (pin "99") (pinfunction "IOR_152_99") (pintype "passive"))
      (node (ref "IC2") (pin "41") (pinfunction "DATA_6_41") (pintype "passive"))
    )
    (net (code "52") (name "/fd7") (class "Default")
      (node (ref "IC1") (pin "98") (pinfunction "IOR_148_98") (pintype "passive"))
      (node (ref "IC2") (pin "42") (pinfunction "DATA_7_42") (pintype "passive"))
    )
    (net (code "53") (name "/fd8") (class "Default")
      (node (ref "IC1") (pin "97") (pinfunction "IOR_147_97") (pintype "passive"))
      (node (ref "IC2") (pin "45") (pinfunction "DATA_8_45") (pintype "passive"))
    )
    (net (code "54") (name "/fd9") (class "Default")
      (node (ref "IC1") (pin "96") (pinfunction "IOR_146_96") (pintype "passive"))
      (node (ref "IC2") (pin "46") (pinfunction "DATA_9_46") (pintype "passive"))
    )
    (net (code "55") (name "/fd10") (class "Default")
      (node (ref "IC1") (pin "95") (pinfunction "IOR_144_95") (pintype "passive"))
      (node (ref "IC2") (pin "47") (pinfunction "DATA_10_47") (pintype "passive"))
    )
    (net (code "56") (name "/fd11") (class "Default")
      (node (ref "IC1") (pin "91") (pinfunction "IOR_139_91") (pintype "passive"))
      (node (ref "IC2") (pin "48") (pinfunction "DATA_11_48") (pintype "passive"))
    )
    (net (code "57") (name "/fd12") (class "Default")
      (node (ref "IC1") (pin "90") (pinfunction "IOR_138_90") (pintype "passive"))
      (node (ref "IC2") (pin "53") (pinfunction "DATA_12_53") (pintype "passive"))
    )
    (net (code "58") (name "/fd13") (class "Default")
      (node (ref "IC1") (pin "88") (pinfunction "IOR_137_88") (pintype "passive"))
      (node (ref "IC2") (pin "54") (pinfunction "DATA_13_54") (pintype "passive"))
    )
    (net (code "59") (name "/fd14") (class "Default")
      (node (ref "IC1") (pin "87") (pinfunction "IOR_136_87") (pintype "passive"))
      (node (ref "IC2") (pin "55") (pinfunction "DATA_14_55") (pintype "passive"))
    )
    (net (code "60") (name "/fd15") (class "Default")
      (node (ref "IC1") (pin "85") (pinfunction "IOR_128_85") (pintype "passive"))
      (node (ref "IC2") (pin "56") (pinfunction "DATA_15_56") (pintype "passive"))
    )
    (net (code "61") (name "/foe") (class "Default")
      (node (ref "IC1") (pin "78") (pinfunction "IOR_114_78") (pintype "passive"))
      (node (ref "IC2") (pin "9") (pinfunction "OE_N_9") (pintype "passive"))
    )
    (net (code "62") (name "/frd") (class "Default")
      (node (ref "IC1") (pin "79") (pinfunction "IOR_115_79") (pintype "passive"))
      (node (ref "IC2") (pin "8") (pinfunction "RD_N_8") (pintype "passive"))
    )
    (net (code "63") (name "/frxf") (class "Default")
      (node (ref "IC1") (pin "81") (pinfunction "IOR_117_81") (pintype "passive"))
      (node (ref "IC2") (pin "5") (pinfunction "RXF_N_5") (pintype "passive"))
    )
    (net (code "64") (name "/ft_adb3") (class "Default")
      (node (ref "IC1") (pin "74") (pinfunction "IOR_110_74") (pintype "passive"))
      (node (ref "IC3") (pin "16") (pinfunction "ADBUS3_16") (pintype "passive"))
    )
    (net (code "65") (name "/ft_adb5") (class "Default")
      (node (ref "IC1") (pin "73") (pinfunction "IOR_109_73") (pintype "passive"))
      (node (ref "IC3") (pin "18") (pinfunction "ADBUS5_18") (pintype "passive"))
    )
    (net (code "66") (name "/ft_cs") (class "Default")
      (node (ref "IC1") (pin "71") (pinfunction "IOB_108_SS_71") (pintype "passive"))
      (node (ref "IC3") (pin "17") (pinfunction "ADBUS4_17") (pintype "passive"))
      (node (ref "IC5") (pin "1") (pinfunction "/CS_1") (pintype "passive"))
      (node (ref "R28") (pin "1") (pinfunction "1_1") (pintype "passive"))
    )
    (net (code "67") (name "/ft_miso") (class "Default")
      (node (ref "IC3") (pin "15") (pinfunction "ADBUS2_15") (pintype "passive"))
      (node (ref "IC5") (pin "2") (pinfunction "DO(IO1)_2") (pintype "passive"))
      (node (ref "JP4") (pin "2") (pinfunction "2_2") (pintype "passive"))
    )
    (net (code "68") (name "/ft_mosi") (class "Default")
      (node (ref "IC3") (pin "14") (pinfunction "ADBUS1_14") (pintype "passive"))
      (node (ref "IC5") (pin "5") (pinfunction "DI(IO0)_5") (pintype "passive"))
      (node (ref "JP3") (pin "1") (pinfunction "1_1") (pintype "passive"))
    )
    (net (code "69") (name "/ft_sck") (class "Default")
      (node (ref "IC1") (pin "70") (pinfunction "IOB_107_SCK_70") (pintype "passive"))
      (node (ref "IC3") (pin "13") (pinfunction "ADBUS0_13") (pintype "passive"))
      (node (ref "IC5") (pin "6") (pinfunction "CLK_6") (pintype "passive"))
      (node (ref "R29") (pin "1") (pinfunction "1_1") (pintype "passive"))
    )
    (net (code "70") (name "/ftxe") (class "Default")
      (node (ref "IC1") (pin "82") (pinfunction "IOR_118_82") (pintype "passive"))
      (node (ref "IC2") (pin "4") (pinfunction "TXE_N_4") (pintype "passive"))
    )
    (net (code "71") (name "/fwr") (class "Default")
      (node (ref "IC1") (pin "80") (pinfunction "IOR_116_80") (pintype "passive"))
      (node (ref "IC2") (pin "7") (pinfunction "WR_N_7") (pintype "passive"))
    )
    (net (code "72") (name "/h_sdi") (class "Default")
      (node (ref "IC1") (pin "68") (pinfunction "IOB_106_SDI_68") (pintype "passive"))
      (node (ref "JP4") (pin "1") (pinfunction "1_1") (pintype "passive"))
    )
    (net (code "73") (name "/h_sdo") (class "Default")
      (node (ref "IC1") (pin "67") (pinfunction "IOB_105_SDO_67") (pintype "passive"))
      (node (ref "JP3") (pin "2") (pinfunction "2_2") (pintype "passive"))
    )
    (net (code "74") (name "/hclk") (class "Default")
      (node (ref "IC1") (pin "94") (pinfunction "IOR_141_GBIN2_94") (pintype "passive"))
      (node (ref "R10") (pin "2") (pinfunction "2_2") (pintype "passive"))
    )
    (net (code "75") (name "/hilo") (class "Default")
      (node (ref "IC1") (pin "34") (pinfunction "IOL_25B_34") (pintype "passive"))
    )
    (net (code "76") (name "/p1_1") (class "Default")
      (node (ref "IC1") (pin "144") (pinfunction "IOT_222_144") (pintype "passive"))
      (node (ref "K1") (pin "1") (pinfunction "1_1") (pintype "passive"))
    )
    (net (code "77") (name "/p1_2") (class "Default")
      (node (ref "IC1") (pin "142") (pinfunction "IOT_220_142") (pintype "passive"))
      (node (ref "K1") (pin "2") (pinfunction "2_2") (pintype "passive"))
    )
    (net (code "78") (name "/p1_3") (class "Default")
      (node (ref "IC1") (pin "139") (pinfunction "IOT_217_139") (pintype "passive"))
      (node (ref "K1") (pin "3") (pinfunction "3_3") (pintype "passive"))
    )
    (net (code "79") (name "/p1_4") (class "Default")
      (node (ref "IC1") (pin "137") (pinfunction "IOT_215_137") (pintype "passive"))
      (node (ref "K1") (pin "4") (pinfunction "4_4") (pintype "passive"))
    )
    (net (code "80") (name "/p1_7") (class "Default")
      (node (ref "IC1") (pin "143") (pinfunction "IOT_221_143") (pintype "passive"))
      (node (ref "K1") (pin "7") (pinfunction "7_7") (pintype "passive"))
    )
    (net (code "81") (name "/p1_8") (class "Default")
      (node (ref "IC1") (pin "141") (pinfunction "IOT_219_141") (pintype "passive"))
      (node (ref "K1") (pin "8") (pinfunction "8_8") (pintype "passive"))
    )
    (net (code "82") (name "/p1_9") (class "Default")
      (node (ref "IC1") (pin "138") (pinfunction "IOT_216_138") (pintype "passive"))
      (node (ref "K1") (pin "9") (pinfunction "9_9") (pintype "passive"))
    )
    (net (code "83") (name "/p1_10") (class "Default")
      (node (ref "IC1") (pin "136") (pinfunction "IOT_214_136") (pintype "passive"))
      (node (ref "K1") (pin "10") (pinfunction "10_10") (pintype "passive"))
    )
    (net (code "84") (name "/p2_1") (class "Default")
      (node (ref "IC1") (pin "135") (pinfunction "IOT_213_135") (pintype "passive"))
      (node (ref "K2") (pin "1") (pinfunction "1_1") (pintype "passive"))
    )
    (net (code "85") (name "/p2_2") (class "Default")
      (node (ref "IC1") (pin "133") (pinfunction "NC_7_133") (pintype "passive"))
      (node (ref "K2") (pin "2") (pinfunction "2_2") (pintype "passive"))
    )
    (net (code "86") (name "/p2_3") (class "Default")
      (node (ref "IC1") (pin "129") (pinfunction "IOT_198_GBIN0_129") (pintype "passive"))
      (node (ref "K2") (pin "3") (pinfunction "3_3") (pintype "passive"))
    )
    (net (code "87") (name "/p2_4") (class "Default")
      (node (ref "IC1") (pin "125") (pinfunction "IOT_192_125") (pintype "passive"))
      (node (ref "K2") (pin "4") (pinfunction "4_4") (pintype "passive"))
    )
    (net (code "88") (name "/p2_7") (class "Default")
      (node (ref "IC1") (pin "134") (pinfunction "IOT_212_134") (pintype "passive"))
      (node (ref "K2") (pin "7") (pinfunction "7_7") (pintype "passive"))
    )
    (net (code "89") (name "/p2_8") (class "Default")
      (node (ref "IC1") (pin "130") (pinfunction "IOT_206_130") (pintype "passive"))
      (node (ref "K2") (pin "8") (pinfunction "8_8") (pintype "passive"))
    )
    (net (code "90") (name "/p2_9") (class "Default")
      (node (ref "IC1") (pin "128") (pinfunction "IOT_197_GBIN1_128") (pintype "passive"))
      (node (ref "K2") (pin "9") (pinfunction "9_9") (pintype "passive"))
    )
    (net (code "91") (name "/p2_10") (class "Default")
      (node (ref "IC1") (pin "124") (pinfunction "IOT_191_124") (pintype "passive"))
      (node (ref "K2") (pin "10") (pinfunction "10_10") (pintype "passive"))
    )
    (net (code "92") (name "/p3_1") (class "Default")
      (node (ref "IC1") (pin "120") (pinfunction "IOT_179_120") (pintype "passive"))
      (node (ref "K3") (pin "1") (pinfunction "1_1") (pintype "passive"))
    )
    (net (code "93") (name "/p3_2") (class "Default")
      (node (ref "IC1") (pin "118") (pinfunction "IOT_177_118") (pintype "passive"))
      (node (ref "K3") (pin "2") (pinfunction "2_2") (pintype "passive"))
    )
    (net (code "94") (name "/p3_3") (class "Default")
      (node (ref "IC1") (pin "116") (pinfunction "IOT_173_116") (pintype "passive"))
      (node (ref "K3") (pin "3") (pinfunction "3_3") (pintype "passive"))
    )
    (net (code "95") (name "/p3_4") (class "Default")
      (node (ref "IC1") (pin "114") (pinfunction "IOT_171_114") (pintype "passive"))
      (node (ref "K3") (pin "4") (pinfunction "4_4") (pintype "passive"))
    )
    (net (code "96") (name "/p3_7") (class "Default")
      (node (ref "IC1") (pin "121") (pinfunction "IOT_181_121") (pintype "passive"))
      (node (ref "K3") (pin "7") (pinfunction "7_7") (pintype "passive"))
    )
    (net (code "97") (name "/p3_8") (class "Default")
      (node (ref "IC1") (pin "119") (pinfunction "IOT_178_119") (pintype "passive"))
      (node (ref "K3") (pin "8") (pinfunction "8_8") (pintype "passive"))
    )
    (net (code "98") (name "/p3_9") (class "Default")
      (node (ref "IC1") (pin "117") (pinfunction "IOT_174_117") (pintype "passive"))
      (node (ref "K3") (pin "9") (pinfunction "9_9") (pintype "passive"))
    )
    (net (code "99") (name "/p3_10") (class "Default")
      (node (ref "IC1") (pin "115") (pinfunction "IOT_172_115") (pintype "passive"))
      (node (ref "K3") (pin "10") (pinfunction "10_10") (pintype "passive"))
    )
    (net (code "100") (name "/p4_1") (class "Default")
      (node (ref "IC1") (pin "44") (pinfunction "IOB_72_44") (pintype "passive"))
      (node (ref "K4") (pin "1") (pinfunction "1_1") (pintype "passive"))
    )
    (net (code "101") (name "/p4_2") (class "Default")
      (node (ref "IC1") (pin "42") (pinfunction "IOB_64_42") (pintype "passive"))
      (node (ref "K4") (pin "2") (pinfunction "2_2") (pintype "passive"))
    )
    (net (code "102") (name "/p4_3") (class "Default")
      (node (ref "IC1") (pin "39") (pinfunction "IOB_61_39") (pintype "passive"))
      (node (ref "K4") (pin "3") (pinfunction "3_3") (pintype "passive"))
    )
    (net (code "103") (name "/p4_4") (class "Default")
      (node (ref "IC1") (pin "37") (pinfunction "IOB_56_37") (pintype "passive"))
      (node (ref "K4") (pin "4") (pinfunction "4_4") (pintype "passive"))
    )
    (net (code "104") (name "/p4_7") (class "Default")
      (node (ref "IC1") (pin "45") (pinfunction "IOB_73_45") (pintype "passive"))
      (node (ref "K4") (pin "7") (pinfunction "7_7") (pintype "passive"))
    )
    (net (code "105") (name "/p4_8") (class "Default")
      (node (ref "IC1") (pin "43") (pinfunction "IOB_71_43") (pintype "passive"))
      (node (ref "K4") (pin "8") (pinfunction "8_8") (pintype "passive"))
    )
    (net (code "106") (name "/p4_9") (class "Default")
      (node (ref "IC1") (pin "41") (pinfunction "IOB_63_41") (pintype "passive"))
      (node (ref "K4") (pin "9") (pinfunction "9_9") (pintype "passive"))
    )
    (net (code "107") (name "/p4_10") (class "Default")
      (node (ref "IC1") (pin "38") (pinfunction "IOB_57_38") (pintype "passive"))
      (node (ref "K4") (pin "10") (pinfunction "10_10") (pintype "passive"))
    )
    (net (code "108") (name "/p5_1") (class "Default")
      (node (ref "IC1") (pin "61") (pinfunction "IOB_96_61") (pintype "passive"))
      (node (ref "K5") (pin "1") (pinfunction "1_1") (pintype "passive"))
    )
    (net (code "109") (name "/p5_2") (class "Default")
      (node (ref "IC1") (pin "56") (pinfunction "IOB_94_56") (pintype "passive"))
      (node (ref "K5") (pin "2") (pinfunction "2_2") (pintype "passive"))
    )
    (net (code "110") (name "/p5_3") (class "Default")
      (node (ref "IC1") (pin "52") (pinfunction "IOB_82_GBIN4_52") (pintype "passive"))
      (node (ref "K5") (pin "3") (pinfunction "3_3") (pintype "passive"))
    )
    (net (code "111") (name "/p5_4") (class "Default")
      (node (ref "IC1") (pin "48") (pinfunction "IOB_80_48") (pintype "passive"))
      (node (ref "K5") (pin "4") (pinfunction "4_4") (pintype "passive"))
    )
    (net (code "112") (name "/p5_7") (class "Default")
      (node (ref "IC1") (pin "60") (pinfunction "IOB_95_60") (pintype "passive"))
      (node (ref "K5") (pin "7") (pinfunction "7_7") (pintype "passive"))
    )
    (net (code "113") (name "/p5_8") (class "Default")
      (node (ref "IC1") (pin "55") (pinfunction "IOB_91_55") (pintype "passive"))
      (node (ref "K5") (pin "8") (pinfunction "8_8") (pintype "passive"))
    )
    (net (code "114") (name "/p5_9") (class "Default")
      (node (ref "IC1") (pin "49") (pinfunction "IOB_81_GBIN5_49") (pintype "passive"))
      (node (ref "K5") (pin "9") (pinfunction "9_9") (pintype "passive"))
    )
    (net (code "115") (name "/p5_10") (class "Default")
      (node (ref "IC1") (pin "47") (pinfunction "IOB_79_47") (pintype "passive"))
      (node (ref "K5") (pin "10") (pinfunction "10_10") (pintype "passive"))
    )
    (net (code "116") (name "/p6_1") (class "Default")
      (node (ref "IC3") (pin "31") (pinfunction "ACBUS7_31") (pintype "passive"))
      (node (ref "K6") (pin "1") (pinfunction "1_1") (pintype "passive"))
    )
    (net (code "117") (name "/p6_2") (class "Default")
      (node (ref "IC3") (pin "29") (pinfunction "ACBUS5_29") (pintype "passive"))
      (node (ref "K6") (pin "2") (pinfunction "2_2") (pintype "passive"))
    )
    (net (code "118") (name "/p6_3") (class "Default")
      (node (ref "IC3") (pin "27") (pinfunction "ACBUS3_27") (pintype "passive"))
      (node (ref "K6") (pin "3") (pinfunction "3_3") (pintype "passive"))
    )
    (net (code "119") (name "/p6_4") (class "Default")
      (node (ref "IC3") (pin "25") (pinfunction "ACBUS1_25") (pintype "passive"))
      (node (ref "K6") (pin "4") (pinfunction "4_4") (pintype "passive"))
    )
    (net (code "120") (name "/p6_7") (class "Default")
      (node (ref "IC3") (pin "30") (pinfunction "ACBUS6_30") (pintype "passive"))
      (node (ref "K6") (pin "7") (pinfunction "7_7") (pintype "passive"))
    )
    (net (code "121") (name "/p6_8") (class "Default")
      (node (ref "IC3") (pin "28") (pinfunction "ACBUS4_28") (pintype "passive"))
      (node (ref "K6") (pin "8") (pinfunction "8_8") (pintype "passive"))
    )
    (net (code "122") (name "/p6_9") (class "Default")
      (node (ref "IC3") (pin "26") (pinfunction "ACBUS2_26") (pintype "passive"))
      (node (ref "K6") (pin "9") (pinfunction "9_9") (pintype "passive"))
    )
    (net (code "123") (name "/p6_10") (class "Default")
      (node (ref "IC3") (pin "21") (pinfunction "ACBUS0_21") (pintype "passive"))
      (node (ref "K6") (pin "10") (pinfunction "10_10") (pintype "passive"))
    )
    (net (code "124") (name "/rx_N") (class "Default")
      (node (ref "IC2") (pin "27") (pinfunction "RIDN_27") (pintype "passive"))
      (node (ref "J1") (pin "9") (pinfunction "9_9") (pintype "passive"))
    )
    (net (code "125") (name "/rx_P") (class "Default")
      (node (ref "IC2") (pin "28") (pinfunction "RIDP_28") (pintype "passive"))
      (node (ref "J1") (pin "10") (pinfunction "10_10") (pintype "passive"))
    )
    (net (code "126") (name "/tx_N") (class "Default")
      (node (ref "C19") (pin "2") (pinfunction "2_2") (pintype "passive"))
      (node (ref "IC2") (pin "24") (pinfunction "TODN_24") (pintype "passive"))
    )
    (net (code "127") (name "/tx_P") (class "Default")
      (node (ref "C22") (pin "2") (pinfunction "2_2") (pintype "passive"))
      (node (ref "IC2") (pin "25") (pinfunction "TODP_25") (pintype "passive"))
    )
    (net (code "128") (name "/vphy") (class "Default")
      (node (ref "C34") (pin "1") (pinfunction "a_1") (pintype "passive"))
      (node (ref "C35") (pin "1") (pinfunction "1_1") (pintype "passive"))
      (node (ref "IC3") (pin "3") (pinfunction "VPHY_3") (pintype "passive"))
      (node (ref "L1") (pin "2") (pinfunction "2_2") (pintype "passive"))
    )
    (net (code "129") (name "/vpll") (class "Default")
      (node (ref "C41") (pin "1") (pinfunction "a_1") (pintype "passive"))
      (node (ref "C42") (pin "1") (pinfunction "1_1") (pintype "passive"))
      (node (ref "IC3") (pin "8") (pinfunction "VPLL_8") (pintype "passive"))
      (node (ref "L2") (pin "2") (pinfunction "2_2") (pintype "passive"))
    )
    (net (code "130") (name "/xi") (class "Default")
      (node (ref "C24") (pin "2") (pinfunction "2_2") (pintype "passive"))
      (node (ref "IC2") (pin "16") (pinfunction "XI_16") (pintype "passive"))
      (node (ref "Y1") (pin "1") (pinfunction "CRYSTAL_1_1") (pintype "passive"))
    )
    (net (code "131") (name "/xo") (class "Default")
      (node (ref "C25") (pin "1") (pinfunction "1_1") (pintype "passive"))
      (node (ref "IC2") (pin "17") (pinfunction "XO_17") (pintype "passive"))
      (node (ref "Y1") (pin "3") (pinfunction "CRYSTAL_2_3") (pintype "passive"))
    )
    (net (code "132") (name "1V2") (class "Default")
      (node (ref "C12") (pin "2") (pinfunction "2_2") (pintype "passive"))
      (node (ref "C13") (pin "2") (pinfunction "2_2") (pintype "passive"))
      (node (ref "C14") (pin "2") (pinfunction "2_2") (pintype "passive"))
      (node (ref "C15") (pin "2") (pinfunction "2_2") (pintype "passive"))
      (node (ref "C38") (pin "1") (pinfunction "1_1") (pintype "passive"))
      (node (ref "IC1") (pin "111") (pinfunction "VCC_4_111") (pintype "passive"))
      (node (ref "IC1") (pin "27") (pinfunction "VCC_1_27") (pintype "passive"))
      (node (ref "IC1") (pin "40") (pinfunction "VCC_2_40") (pintype "passive"))
      (node (ref "IC1") (pin "92") (pinfunction "VCC_3_92") (pintype "passive"))
      (node (ref "PS2") (pin "2") (pinfunction "VOUT_2") (pintype "output"))
      (node (ref "R7") (pin "1") (pinfunction "1_1") (pintype "passive"))
      (node (ref "R8") (pin "1") (pinfunction "1_1") (pintype "passive"))
      (node (ref "SP4") (pin "1") (pinfunction "1_1") (pintype "passive"))
    )
    (net (code "133") (name "2V5") (class "Default")
      (node (ref "D1") (pin "2") (pinfunction "k_2") (pintype "passive"))
      (node (ref "IC1") (pin "108") (pinfunction "VPP_2V5_108") (pintype "passive"))
    )
    (net (code "134") (name "3V3_1") (class "Default")
      (node (ref "C32") (pin "1") (pinfunction "a_1") (pintype "passive"))
      (node (ref "C33") (pin "1") (pinfunction "1_1") (pintype "passive"))
      (node (ref "C40") (pin "2") (pinfunction "2_2") (pintype "passive"))
      (node (ref "IC3") (pin "12") (pinfunction "VCCIO_1_12") (pintype "passive"))
      (node (ref "IC3") (pin "24") (pinfunction "VCCIO_2_24") (pintype "passive"))
      (node (ref "IC3") (pin "34") (pinfunction "~{RESET}_34") (pintype "passive"))
      (node (ref "IC3") (pin "39") (pinfunction "VCCD_39") (pintype "passive"))
      (node (ref "IC3") (pin "46") (pinfunction "VCCIO_3_46") (pintype "passive"))
      (node (ref "IC4") (pin "6") (pinfunction "VCC_6") (pintype "passive"))
      (node (ref "L1") (pin "1") (pinfunction "1_1") (pintype "passive"))
      (node (ref "L2") (pin "1") (pinfunction "1_1") (pintype "passive"))
      (node (ref "R17") (pin "2") (pinfunction "2_2") (pintype "passive"))
      (node (ref "R18") (pin "2") (pinfunction "2_2") (pintype "passive"))
      (node (ref "R19") (pin "2") (pinfunction "2_2") (pintype "passive"))
    )
    (net (code "135") (name "GND") (class "Default")
      (node (ref "C1") (pin "1") (pinfunction "1_1") (pintype "passive"))
      (node (ref "C10") (pin "1") (pinfunction "1_1") (pintype "passive"))
      (node (ref "C11") (pin "2") (pinfunction "2_2") (pintype "passive"))
      (node (ref "C12") (pin "1") (pinfunction "1_1") (pintype "passive"))
      (node (ref "C13") (pin "1") (pinfunction "1_1") (pintype "passive"))
      (node (ref "C14") (pin "1") (pinfunction "1_1") (pintype "passive"))
      (node (ref "C15") (pin "1") (pinfunction "1_1") (pintype "passive"))
      (node (ref "C17") (pin "1") (pinfunction "1_1") (pintype "passive"))
      (node (ref "C2") (pin "1") (pinfunction "1_1") (pintype "passive"))
      (node (ref "C20") (pin "1") (pinfunction "1_1") (pintype "passive"))
      (node (ref "C21") (pin "1") (pinfunction "1_1") (pintype "passive"))
      (node (ref "C23") (pin "2") (pinfunction "2_2") (pintype "passive"))
      (node (ref "C24") (pin "1") (pinfunction "1_1") (pintype "passive"))
      (node (ref "C25") (pin "2") (pinfunction "2_2") (pintype "passive"))
      (node (ref "C26") (pin "2") (pinfunction "2_2") (pintype "passive"))
      (node (ref "C27") (pin "2") (pinfunction "2_2") (pintype "passive"))
      (node (ref "C28") (pin "2") (pinfunction "2_2") (pintype "passive"))
      (node (ref "C29") (pin "1") (pinfunction "1_1") (pintype "passive"))
      (node (ref "C3") (pin "1") (pinfunction "1_1") (pintype "passive"))
      (node (ref "C30") (pin "2") (pinfunction "b_2") (pintype "passive"))
      (node (ref "C31") (pin "2") (pinfunction "2_2") (pintype "passive"))
      (node (ref "C32") (pin "2") (pinfunction "b_2") (pintype "passive"))
      (node (ref "C33") (pin "2") (pinfunction "2_2") (pintype "passive"))
      (node (ref "C34") (pin "2") (pinfunction "b_2") (pintype "passive"))
      (node (ref "C35") (pin "2") (pinfunction "2_2") (pintype "passive"))
      (node (ref "C36") (pin "2") (pinfunction "2_2") (pintype "passive"))
      (node (ref "C37") (pin "2") (pinfunction "2_2") (pintype "passive"))
      (node (ref "C38") (pin "2") (pinfunction "2_2") (pintype "passive"))
      (node (ref "C39") (pin "1") (pinfunction "1_1") (pintype "passive"))
      (node (ref "C4") (pin "1") (pinfunction "1_1") (pintype "passive"))
      (node (ref "C40") (pin "1") (pinfunction "1_1") (pintype "passive"))
      (node (ref "C41") (pin "2") (pinfunction "b_2") (pintype "passive"))
      (node (ref "C42") (pin "2") (pinfunction "2_2") (pintype "passive"))
      (node (ref "C44") (pin "2") (pinfunction "2_2") (pintype "passive"))
      (node (ref "C45") (pin "1") (pinfunction "1_1") (pintype "passive"))
      (node (ref "C5") (pin "1") (pinfunction "1_1") (pintype "passive"))
      (node (ref "C6") (pin "1") (pinfunction "1_1") (pintype "passive"))
      (node (ref "C68") (pin "1") (pinfunction "1_1") (pintype "passive"))
      (node (ref "C69") (pin "1") (pinfunction "1_1") (pintype "passive"))
      (node (ref "C7") (pin "1") (pinfunction "1_1") (pintype "passive"))
      (node (ref "C8") (pin "1") (pinfunction "1_1") (pintype "passive"))
      (node (ref "C9") (pin "1") (pinfunction "1_1") (pintype "passive"))
      (node (ref "D6") (pin "2") (pinfunction "k_2") (pintype "passive"))
      (node (ref "IC1") (pin "103") (pinfunction "GND_7_103") (pintype "passive"))
      (node (ref "IC1") (pin "13") (pinfunction "GND_2_13") (pintype "passive"))
      (node (ref "IC1") (pin "132") (pinfunction "GND_8_132") (pintype "passive"))
      (node (ref "IC1") (pin "14") (pinfunction "GND_3_14") (pintype "passive"))
      (node (ref "IC1") (pin "140") (pinfunction "GND_9_140") (pintype "passive"))
      (node (ref "IC1") (pin "5") (pinfunction "GND_1_5") (pintype "passive"))
      (node (ref "IC1") (pin "59") (pinfunction "GND_4_59") (pintype "passive"))
      (node (ref "IC1") (pin "69") (pinfunction "GND_5_69") (pintype "passive"))
      (node (ref "IC1") (pin "86") (pinfunction "GND_6_86") (pintype "passive"))
      (node (ref "IC2") (pin "32") (pinfunction "GND_1_32") (pintype "passive"))
      (node (ref "IC2") (pin "49") (pinfunction "GND_2_49") (pintype "passive"))
      (node (ref "IC2") (pin "51") (pinfunction "GND_3_51") (pintype "passive"))
      (node (ref "IC2") (pin "57") (pinfunction "THERMAL_PAD_57") (pintype "passive"))
      (node (ref "IC3") (pin "10") (pinfunction "GND_1_10") (pintype "passive"))
      (node (ref "IC3") (pin "11") (pinfunction "GND_2_11") (pintype "passive"))
      (node (ref "IC3") (pin "22") (pinfunction "GND_3_22") (pintype "passive"))
      (node (ref "IC3") (pin "23") (pinfunction "GND_4_23") (pintype "passive"))
      (node (ref "IC3") (pin "35") (pinfunction "GND_5_35") (pintype "passive"))
      (node (ref "IC3") (pin "36") (pinfunction "GND_6_36") (pintype "passive"))
      (node (ref "IC3") (pin "4") (pinfunction "AGND_1_4") (pintype "passive"))
      (node (ref "IC3") (pin "41") (pinfunction "AGND_3_41") (pintype "passive"))
      (node (ref "IC3") (pin "42") (pinfunction "TEST_42") (pintype "passive"))
      (node (ref "IC3") (pin "47") (pinfunction "GND_7_47") (pintype "passive"))
      (node (ref "IC3") (pin "48") (pinfunction "GND_8_48") (pintype "passive"))
      (node (ref "IC3") (pin "9") (pinfunction "AGND_2_9") (pintype "passive"))
      (node (ref "IC4") (pin "2") (pinfunction "VSS_2") (pintype "passive"))
      (node (ref "IC5") (pin "4") (pinfunction "GND_4") (pintype "passive"))
      (node (ref "J1") (pin "5") (pinfunction "5_5") (pintype "passive"))
      (node (ref "J1") (pin "8") (pinfunction "8_8") (pintype "passive"))
      (node (ref "J1") (pin "MH1") (pinfunction "MH1_MH1") (pintype "passive"))
      (node (ref "J1") (pin "MH2") (pinfunction "MH2_MH2") (pintype "passive"))
      (node (ref "J1") (pin "MH3") (pinfunction "MH3_MH3") (pintype "passive"))
      (node (ref "J1") (pin "MH4") (pinfunction "MH4_MH4") (pintype "passive"))
      (node (ref "J1") (pin "MH5") (pinfunction "MH5_MH5") (pintype "passive"))
      (node (ref "J1") (pin "MP1") (pinfunction "MP1_MP1") (pintype "passive"))
      (node (ref "J2") (pin "5") (pinfunction "5_5") (pintype "passive"))
      (node (ref "J2") (pin "MH1") (pinfunction "MH1_MH1") (pintype "passive"))
      (node (ref "J2") (pin "MH2") (pinfunction "MH2_MH2") (pintype "passive"))
      (node (ref "J2") (pin "MH3") (pinfunction "MH3_MH3") (pintype "passive"))
      (node (ref "J2") (pin "MH4") (pinfunction "MH4_MH4") (pintype "passive"))
      (node (ref "JP5") (pin "2") (pinfunction "2_2") (pintype "passive"))
      (node (ref "K1") (pin "11") (pinfunction "gnd_11") (pintype "passive"))
      (node (ref "K1") (pin "5") (pinfunction "gnd_5") (pintype "passive"))
      (node (ref "K2") (pin "11") (pinfunction "gnd_11") (pintype "passive"))
      (node (ref "K2") (pin "5") (pinfunction "gnd_5") (pintype "passive"))
      (node (ref "K3") (pin "11") (pinfunction "gnd_11") (pintype "passive"))
      (node (ref "K3") (pin "5") (pinfunction "gnd_5") (pintype "passive"))
      (node (ref "K4") (pin "11") (pinfunction "gnd_11") (pintype "passive"))
      (node (ref "K4") (pin "5") (pinfunction "gnd_5") (pintype "passive"))
      (node (ref "K5") (pin "11") (pinfunction "gnd_11") (pintype "passive"))
      (node (ref "K5") (pin "5") (pinfunction "gnd_5") (pintype "passive"))
      (node (ref "K6") (pin "11") (pinfunction "gnd_11") (pintype "passive"))
      (node (ref "K6") (pin "5") (pinfunction "gnd_5") (pintype "passive"))
      (node (ref "PS1") (pin "1") (pinfunction "GND_1") (pintype "power_in"))
      (node (ref "PS2") (pin "1") (pinfunction "GND_1") (pintype "power_in"))
      (node (ref "PS3") (pin "1") (pinfunction "GND_1") (pintype "power_in"))
      (node (ref "R12") (pin "1") (pinfunction "1_1") (pintype "passive"))
      (node (ref "R30") (pin "1") (pinfunction "1_1") (pintype "passive"))
      (node (ref "R5") (pin "1") (pinfunction "1_1") (pintype "passive"))
      (node (ref "R6") (pin "1") (pinfunction "1_1") (pintype "passive"))
      (node (ref "R9") (pin "1") (pinfunction "1_1") (pintype "passive"))
      (node (ref "U3") (pin "2") (pinfunction "gnd_2") (pintype "passive"))
      (node (ref "Y1") (pin "2") (pinfunction "GND_1_2") (pintype "passive"))
      (node (ref "Y1") (pin "4") (pinfunction "GND_2_4") (pintype "passive"))
      (node (ref "Y2") (pin "2") (pinfunction "GND_2") (pintype "passive"))
    )
    (net (code "136") (name "Net-(C19-Pad1)") (class "Default")
      (node (ref "C19") (pin "1") (pinfunction "1_1") (pintype "passive"))
      (node (ref "J1") (pin "6") (pinfunction "6_6") (pintype "passive"))
    )
    (net (code "137") (name "Net-(C22-Pad1)") (class "Default")
      (node (ref "C22") (pin "1") (pinfunction "1_1") (pintype "passive"))
      (node (ref "J1") (pin "7") (pinfunction "7_7") (pintype "passive"))
    )
    (net (code "138") (name "Net-(D5-a)") (class "Default")
      (node (ref "D5") (pin "1") (pinfunction "a_1") (pintype "passive"))
      (node (ref "L9") (pin "2") (pinfunction "2_2") (pintype "passive"))
      (node (ref "U3") (pin "1") (pinfunction "sw_1") (pintype "passive"))
    )
    (net (code "139") (name "Net-(IC2-GPIO0)") (class "Default")
      (node (ref "IC2") (pin "12") (pinfunction "GPIO0_12") (pintype "passive"))
      (node (ref "JP1") (pin "2") (pinfunction "2_2") (pintype "passive"))
      (node (ref "R5") (pin "2") (pinfunction "2_2") (pintype "passive"))
    )
    (net (code "140") (name "Net-(IC2-GPIO1)") (class "Default")
      (node (ref "IC2") (pin "13") (pinfunction "GPIO1_13") (pintype "passive"))
      (node (ref "JP2") (pin "2") (pinfunction "2_2") (pintype "passive"))
      (node (ref "R6") (pin "2") (pinfunction "2_2") (pintype "passive"))
    )
    (net (code "141") (name "Net-(IC2-RESET_N)") (class "Default")
      (node (ref "C11") (pin "1") (pinfunction "1_1") (pintype "passive"))
      (node (ref "IC2") (pin "10") (pinfunction "RESET_N_10") (pintype "passive"))
      (node (ref "R3") (pin "1") (pinfunction "1_1") (pintype "passive"))
    )
    (net (code "142") (name "Net-(IC2-RREF)") (class "Default")
      (node (ref "IC2") (pin "21") (pinfunction "RREF_21") (pintype "passive"))
      (node (ref "R9") (pin "2") (pinfunction "2_2") (pintype "passive"))
    )
    (net (code "143") (name "Net-(IC2-SIWU_N)") (class "Default")
      (node (ref "IC2") (pin "6") (pinfunction "SIWU_N_6") (pintype "passive"))
      (node (ref "R4") (pin "1") (pinfunction "1_1") (pintype "passive"))
    )
    (net (code "144") (name "Net-(IC2-WAKEUP_N)") (class "Default")
      (node (ref "IC2") (pin "11") (pinfunction "WAKEUP_N_11") (pintype "passive"))
      (node (ref "R2") (pin "1") (pinfunction "1_1") (pintype "passive"))
    )
    (net (code "145") (name "Net-(IC3-REF)") (class "Default")
      (node (ref "IC3") (pin "5") (pinfunction "REF_5") (pintype "passive"))
      (node (ref "R12") (pin "2") (pinfunction "2_2") (pintype "passive"))
    )
    (net (code "146") (name "Net-(IC3-VCCA)") (class "Default")
      (node (ref "C28") (pin "1") (pinfunction "1_1") (pintype "passive"))
      (node (ref "IC3") (pin "37") (pinfunction "VCCA_37") (pintype "passive"))
    )
    (net (code "147") (name "Net-(IC3-VCCCORE)") (class "Default")
      (node (ref "C27") (pin "1") (pinfunction "1_1") (pintype "passive"))
      (node (ref "IC3") (pin "38") (pinfunction "VCCCORE_38") (pintype "passive"))
    )
    (net (code "148") (name "Net-(IC3-XCSI)") (class "Default")
      (node (ref "IC3") (pin "1") (pinfunction "XCSI_1") (pintype "passive"))
      (node (ref "R11") (pin "2") (pinfunction "2_2") (pintype "passive"))
    )
    (net (code "149") (name "Net-(IC4-DO)") (class "Default")
      (node (ref "IC4") (pin "1") (pinfunction "DO_1") (pintype "passive"))
      (node (ref "R17") (pin "1") (pinfunction "1_1") (pintype "passive"))
      (node (ref "R20") (pin "2") (pinfunction "2_2") (pintype "passive"))
    )
    (net (code "150") (name "Net-(JP1-Pad1)") (class "Default")
      (node (ref "JP1") (pin "1") (pinfunction "1_1") (pintype "passive"))
      (node (ref "JP2") (pin "1") (pinfunction "1_1") (pintype "passive"))
      (node (ref "R1") (pin "1") (pinfunction "1_1") (pintype "passive"))
    )
    (net (code "151") (name "Net-(LED1-BLUE_(CATHODE))") (class "Default")
      (node (ref "LED1") (pin "3") (pinfunction "BLUE_(CATHODE)_3") (pintype "passive"))
      (node (ref "R14") (pin "1") (pinfunction "1_1") (pintype "passive"))
    )
    (net (code "152") (name "Net-(LED1-GREEN_(CATHODE))") (class "Default")
      (node (ref "LED1") (pin "4") (pinfunction "GREEN_(CATHODE)_4") (pintype "passive"))
      (node (ref "R15") (pin "1") (pinfunction "1_1") (pintype "passive"))
    )
    (net (code "153") (name "Net-(LED1-RED_(CATHODE))") (class "Default")
      (node (ref "LED1") (pin "1") (pinfunction "RED_(CATHODE)_1") (pintype "passive"))
      (node (ref "R13") (pin "2") (pinfunction "2_2") (pintype "passive"))
    )
    (net (code "154") (name "Net-(U3-fb)") (class "Default")
      (node (ref "R27") (pin "1") (pinfunction "1_1") (pintype "passive"))
      (node (ref "R30") (pin "2") (pinfunction "2_2") (pintype "passive"))
      (node (ref "U3") (pin "3") (pinfunction "fb_3") (pintype "passive"))
    )
    (net (code "155") (name "Net-(Y2-OUTPUT)") (class "Default")
      (node (ref "R10") (pin "1") (pinfunction "1_1") (pintype "passive"))
      (node (ref "R11") (pin "1") (pinfunction "1_1") (pintype "passive"))
      (node (ref "Y2") (pin "3") (pinfunction "OUTPUT_3") (pintype "passive"))
    )
    (net (code "156") (name "unconnected-(IC1-IOB_102-Pad62)") (class "Default")
      (node (ref "IC1") (pin "62") (pinfunction "IOB_102_62") (pintype "passive"))
    )
    (net (code "157") (name "unconnected-(IC1-IOB_103_CBSEL0-Pad63)") (class "Default")
      (node (ref "IC1") (pin "63") (pinfunction "IOB_103_CBSEL0_63") (pintype "passive"))
    )
    (net (code "158") (name "unconnected-(IC1-IOB_104_CBSEL1-Pad64)") (class "Default")
      (node (ref "IC1") (pin "64") (pinfunction "IOB_104_CBSEL1_64") (pintype "passive"))
    )
    (net (code "159") (name "unconnected-(IC1-IOL_3A-Pad3)") (class "Default")
      (node (ref "IC1") (pin "3") (pinfunction "IOL_3A_3") (pintype "passive"))
    )
    (net (code "160") (name "unconnected-(IC1-IOL_4B-Pad8)") (class "Default")
      (node (ref "IC1") (pin "8") (pinfunction "IOL_4B_8") (pintype "passive"))
    )
    (net (code "161") (name "unconnected-(IC1-IOL_5B-Pad10)") (class "Default")
      (node (ref "IC1") (pin "10") (pinfunction "IOL_5B_10") (pintype "passive"))
    )
    (net (code "162") (name "unconnected-(IC1-IOL_8B-Pad12)") (class "Default")
      (node (ref "IC1") (pin "12") (pinfunction "IOL_8B_12") (pintype "passive"))
    )
    (net (code "163") (name "unconnected-(IC1-IOL_10B-Pad16)") (class "Default")
      (node (ref "IC1") (pin "16") (pinfunction "IOL_10B_16") (pintype "passive"))
    )
    (net (code "164") (name "unconnected-(IC1-IOL_12A-Pad17)") (class "Default")
      (node (ref "IC1") (pin "17") (pinfunction "IOL_12A_17") (pintype "passive"))
    )
    (net (code "165") (name "unconnected-(IC1-IOL_12B-Pad18)") (class "Default")
      (node (ref "IC1") (pin "18") (pinfunction "IOL_12B_18") (pintype "passive"))
    )
    (net (code "166") (name "unconnected-(IC1-IOL_13A-Pad19)") (class "Default")
      (node (ref "IC1") (pin "19") (pinfunction "IOL_13A_19") (pintype "passive"))
    )
    (net (code "167") (name "unconnected-(IC1-IOL_14B-Pad22)") (class "Default")
      (node (ref "IC1") (pin "22") (pinfunction "IOL_14B_22") (pintype "passive"))
    )
    (net (code "168") (name "unconnected-(IC1-IOR_111-Pad75)") (class "Default")
      (node (ref "IC1") (pin "75") (pinfunction "IOR_111_75") (pintype "passive"))
    )
    (net (code "169") (name "unconnected-(IC1-IOR_112-Pad76)") (class "Default")
      (node (ref "IC1") (pin "76") (pinfunction "IOR_112_76") (pintype "passive"))
    )
    (net (code "170") (name "unconnected-(IC1-IOT_190-Pad122)") (class "Default")
      (node (ref "IC1") (pin "122") (pinfunction "IOT_190_122") (pintype "passive"))
    )
    (net (code "171") (name "unconnected-(IC1-NC_1-Pad35)") (class "Default")
      (node (ref "IC1") (pin "35") (pinfunction "NC_1_35") (pintype "passive"))
    )
    (net (code "172") (name "unconnected-(IC1-NC_2-Pad36)") (class "Default")
      (node (ref "IC1") (pin "36") (pinfunction "NC_2_36") (pintype "passive"))
    )
    (net (code "173") (name "unconnected-(IC1-NC_3-Pad50)") (class "Default")
      (node (ref "IC1") (pin "50") (pinfunction "NC_3_50") (pintype "passive"))
    )
    (net (code "174") (name "unconnected-(IC1-NC_4-Pad51)") (class "Default")
      (node (ref "IC1") (pin "51") (pinfunction "NC_4_51") (pintype "passive"))
    )
    (net (code "175") (name "unconnected-(IC1-NC_5-Pad58)") (class "Default")
      (node (ref "IC1") (pin "58") (pinfunction "NC_5_58") (pintype "passive"))
    )
    (net (code "176") (name "unconnected-(IC1-NC_6-Pad77)") (class "Default")
      (node (ref "IC1") (pin "77") (pinfunction "NC_6_77") (pintype "passive"))
    )
    (net (code "177") (name "unconnected-(IC1-VPP_FAST-Pad109)") (class "Default")
      (node (ref "IC1") (pin "109") (pinfunction "VPP_FAST_109") (pintype "passive"))
    )
    (net (code "178") (name "unconnected-(IC2-RESERVE-Pad14)") (class "Default")
      (node (ref "IC2") (pin "14") (pinfunction "RESERVE_14") (pintype "passive"))
    )
    (net (code "179") (name "unconnected-(IC3-ACBUS8-Pad32)") (class "Default")
      (node (ref "IC3") (pin "32") (pinfunction "ACBUS8_32") (pintype "passive"))
    )
    (net (code "180") (name "unconnected-(IC3-ACBUS9-Pad33)") (class "Default")
      (node (ref "IC3") (pin "33") (pinfunction "ACBUS9_33") (pintype "passive"))
    )
    (net (code "181") (name "unconnected-(IC3-XCSO-Pad2)") (class "Default")
      (node (ref "IC3") (pin "2") (pinfunction "XCSO_2") (pintype "passive"))
    )
    (net (code "182") (name "unconnected-(J1-Pad4)") (class "Default")
      (node (ref "J1") (pin "4") (pinfunction "4_4") (pintype "passive"))
    )
    (net (code "183") (name "unconnected-(J2-Pad4)") (class "Default")
      (node (ref "J2") (pin "4") (pinfunction "4_4") (pintype "passive"))
    )
    (net (code "184") (name "unconnected-(Y2-TRI-STATE-Pad1)") (class "Default")
      (node (ref "Y2") (pin "1") (pinfunction "TRI-STATE_1") (pintype "passive"))
    )
  )
)
